# Module_BaseBoard.net
KiCad netlist of a schematic drawn in EAGLE
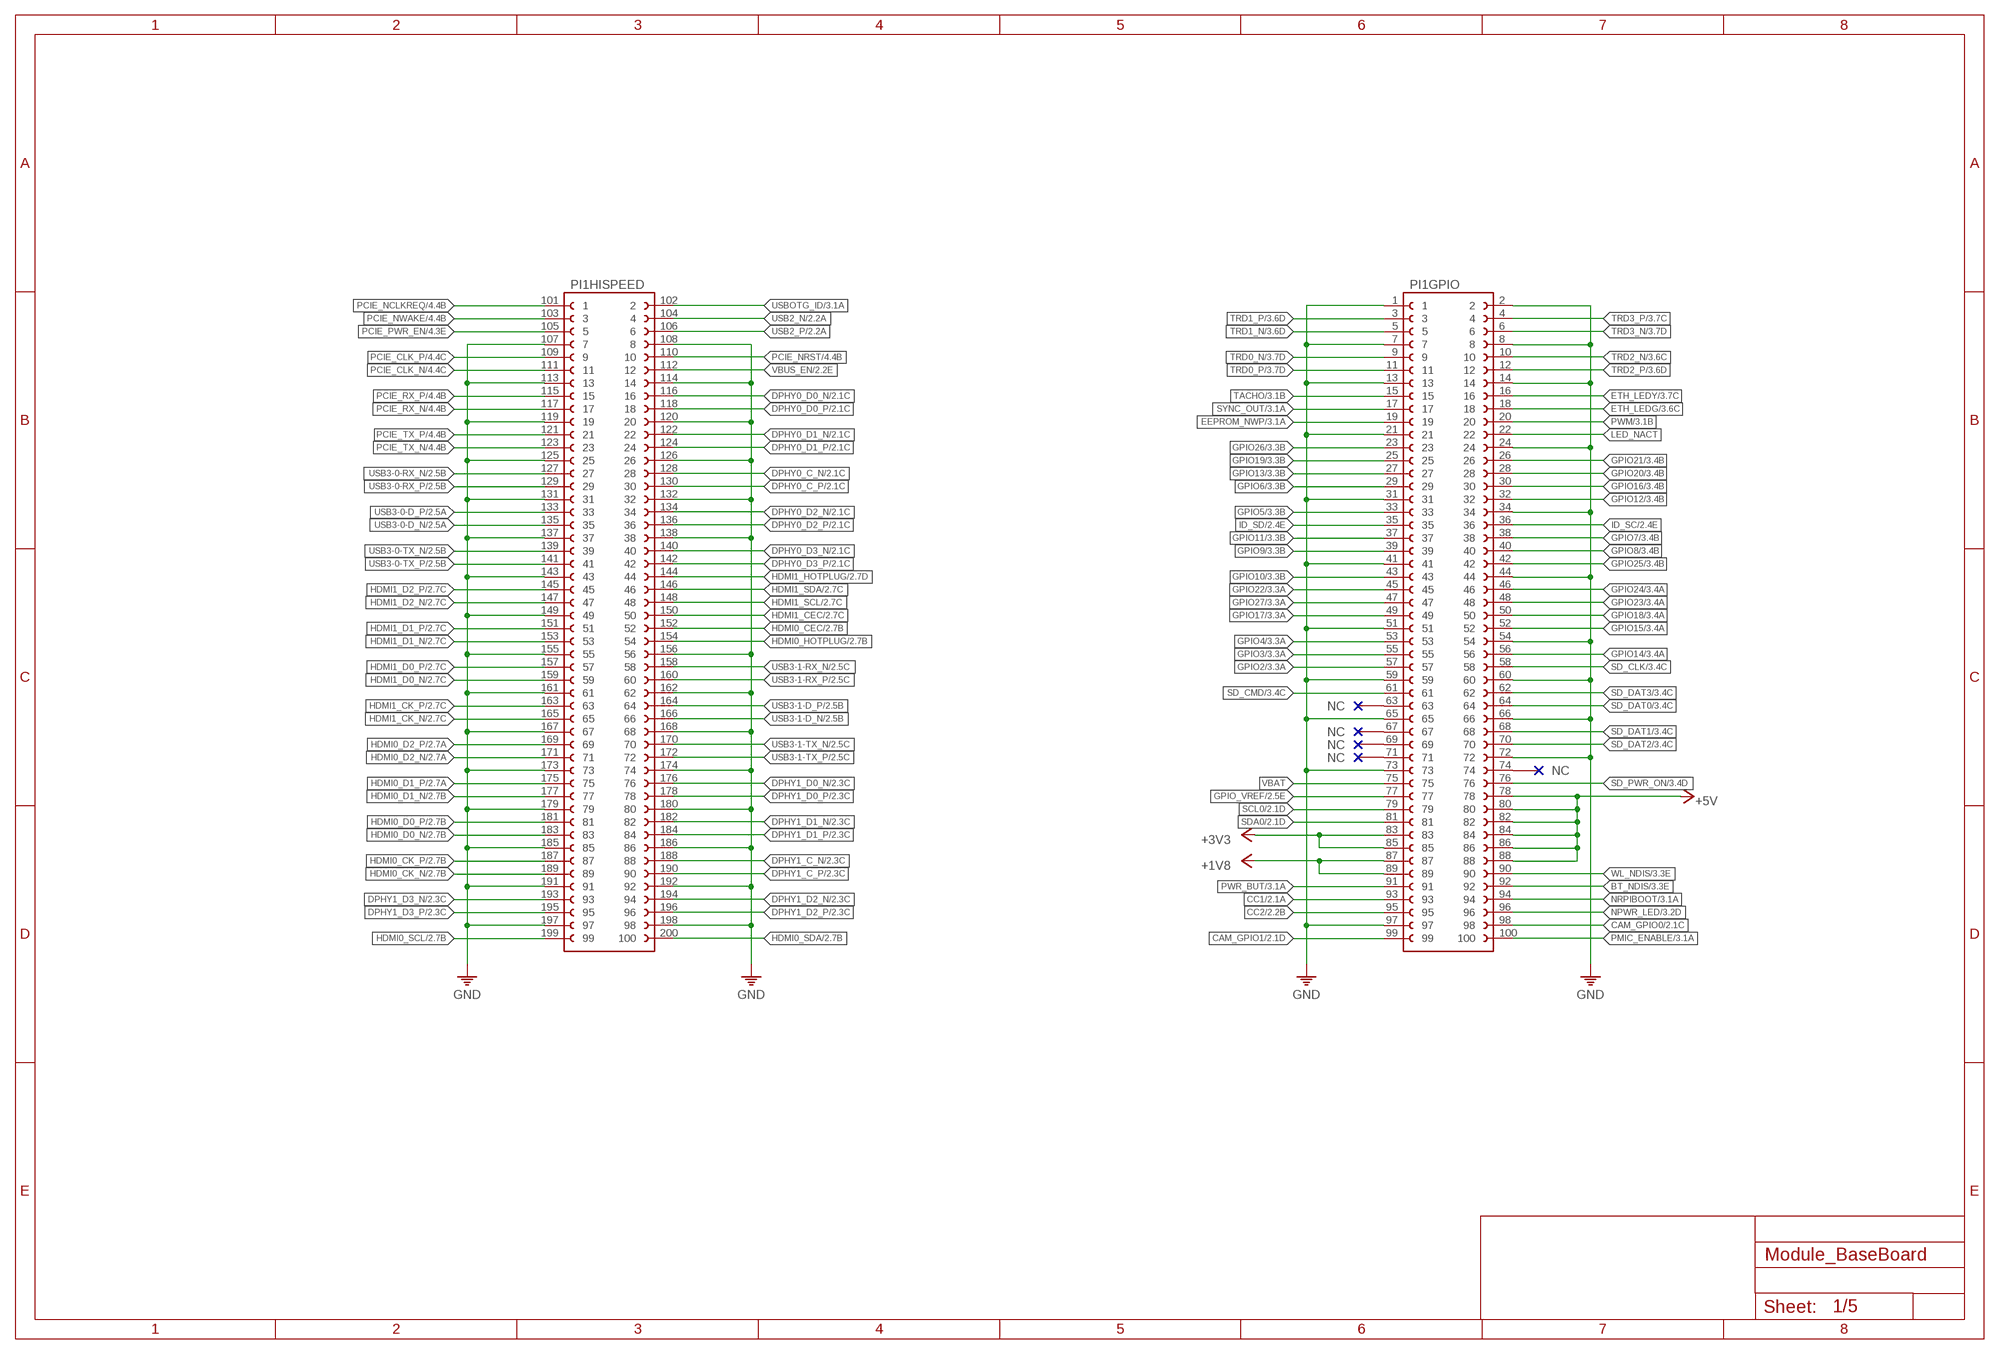
[diagram p0: schematic, sheet 1]
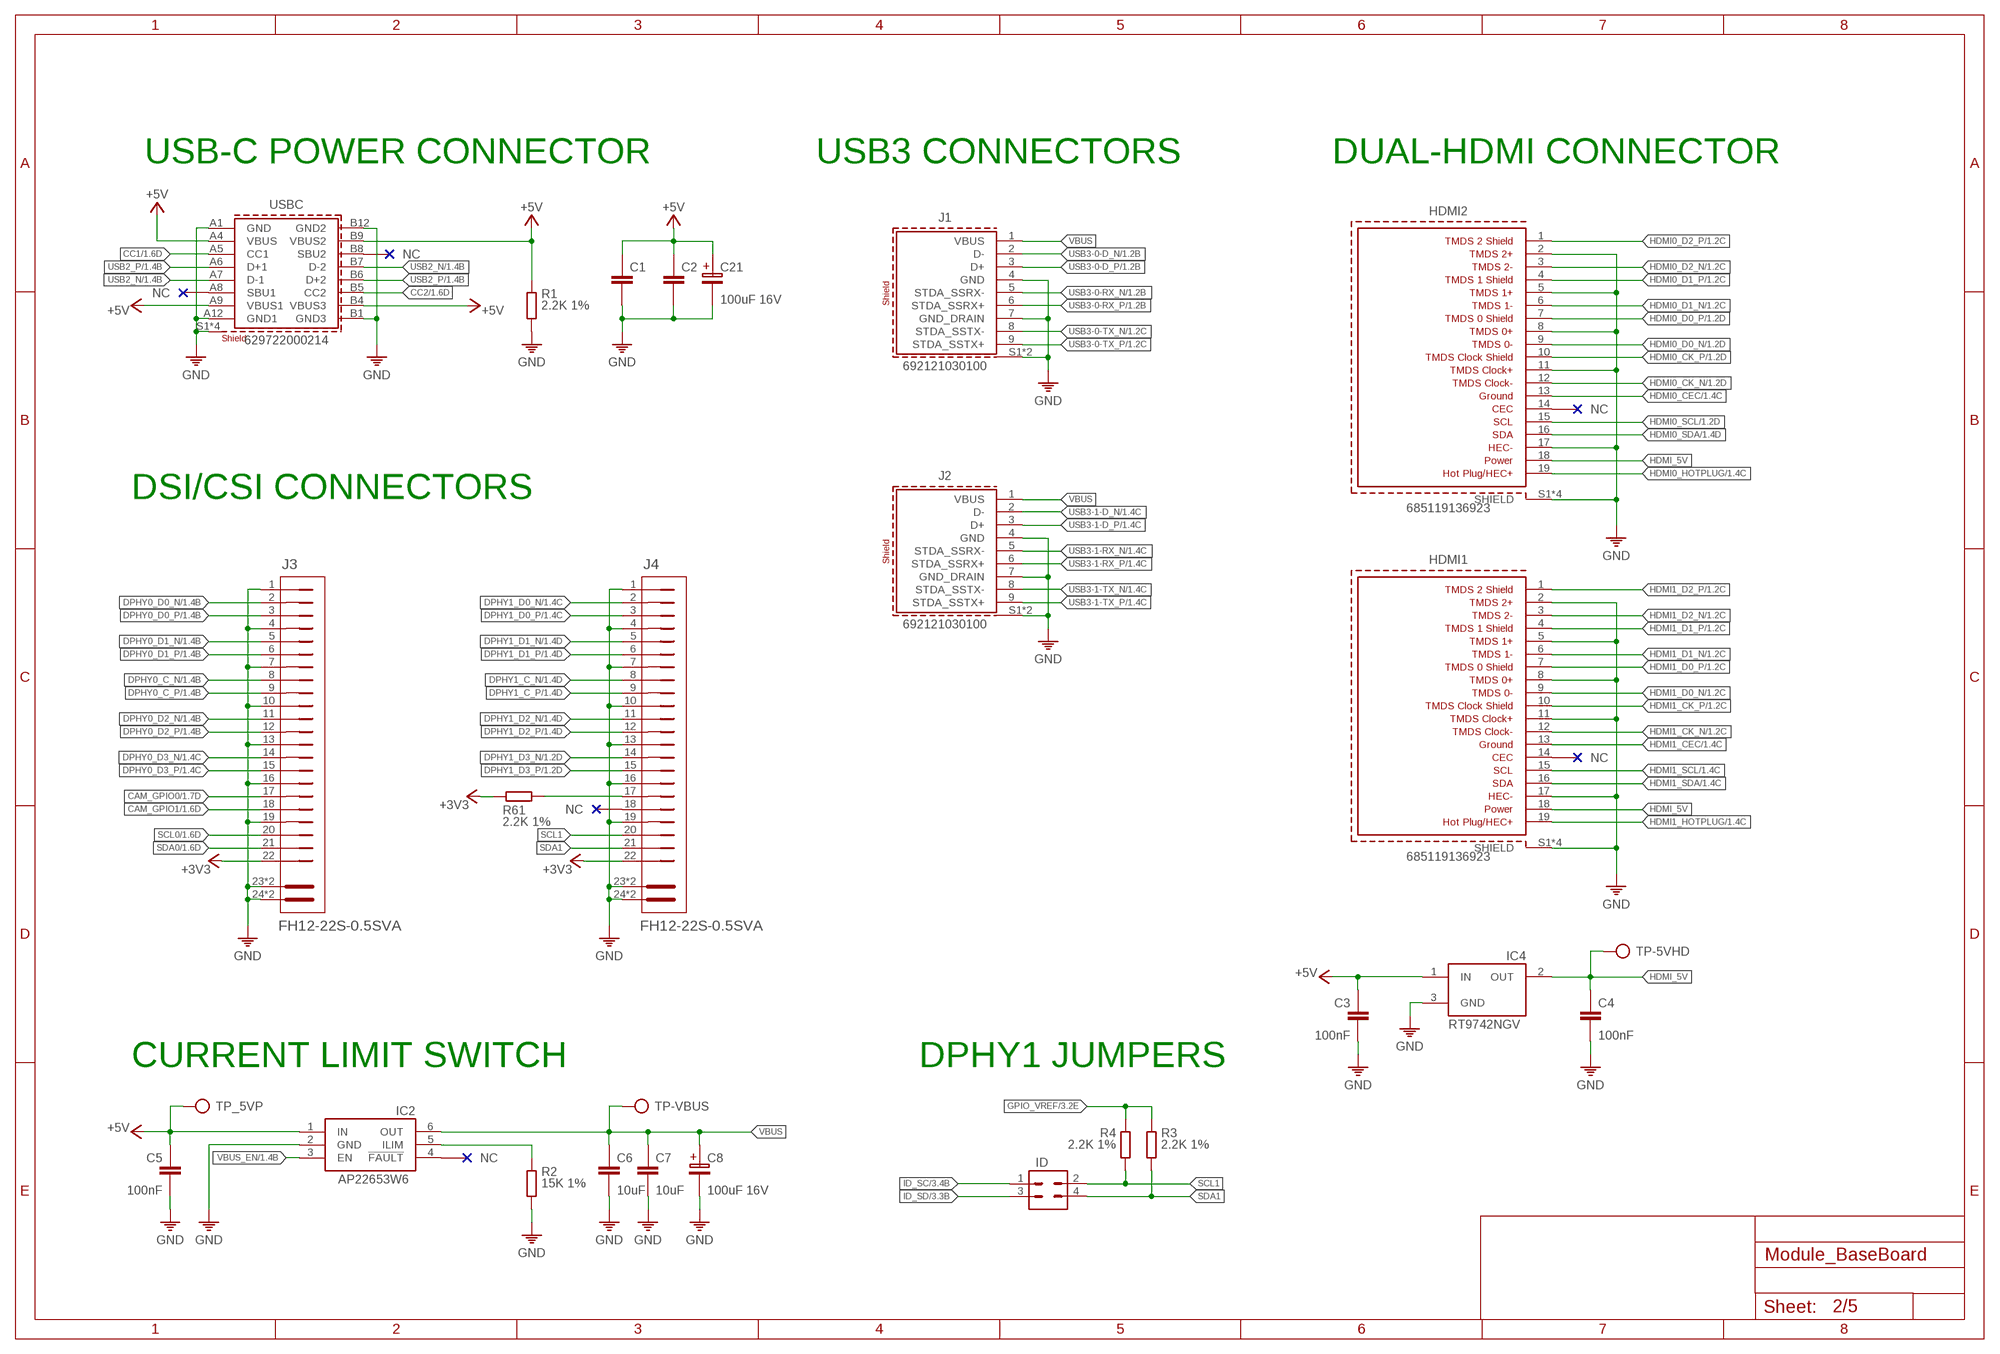
[diagram p1: schematic, sheet 2]
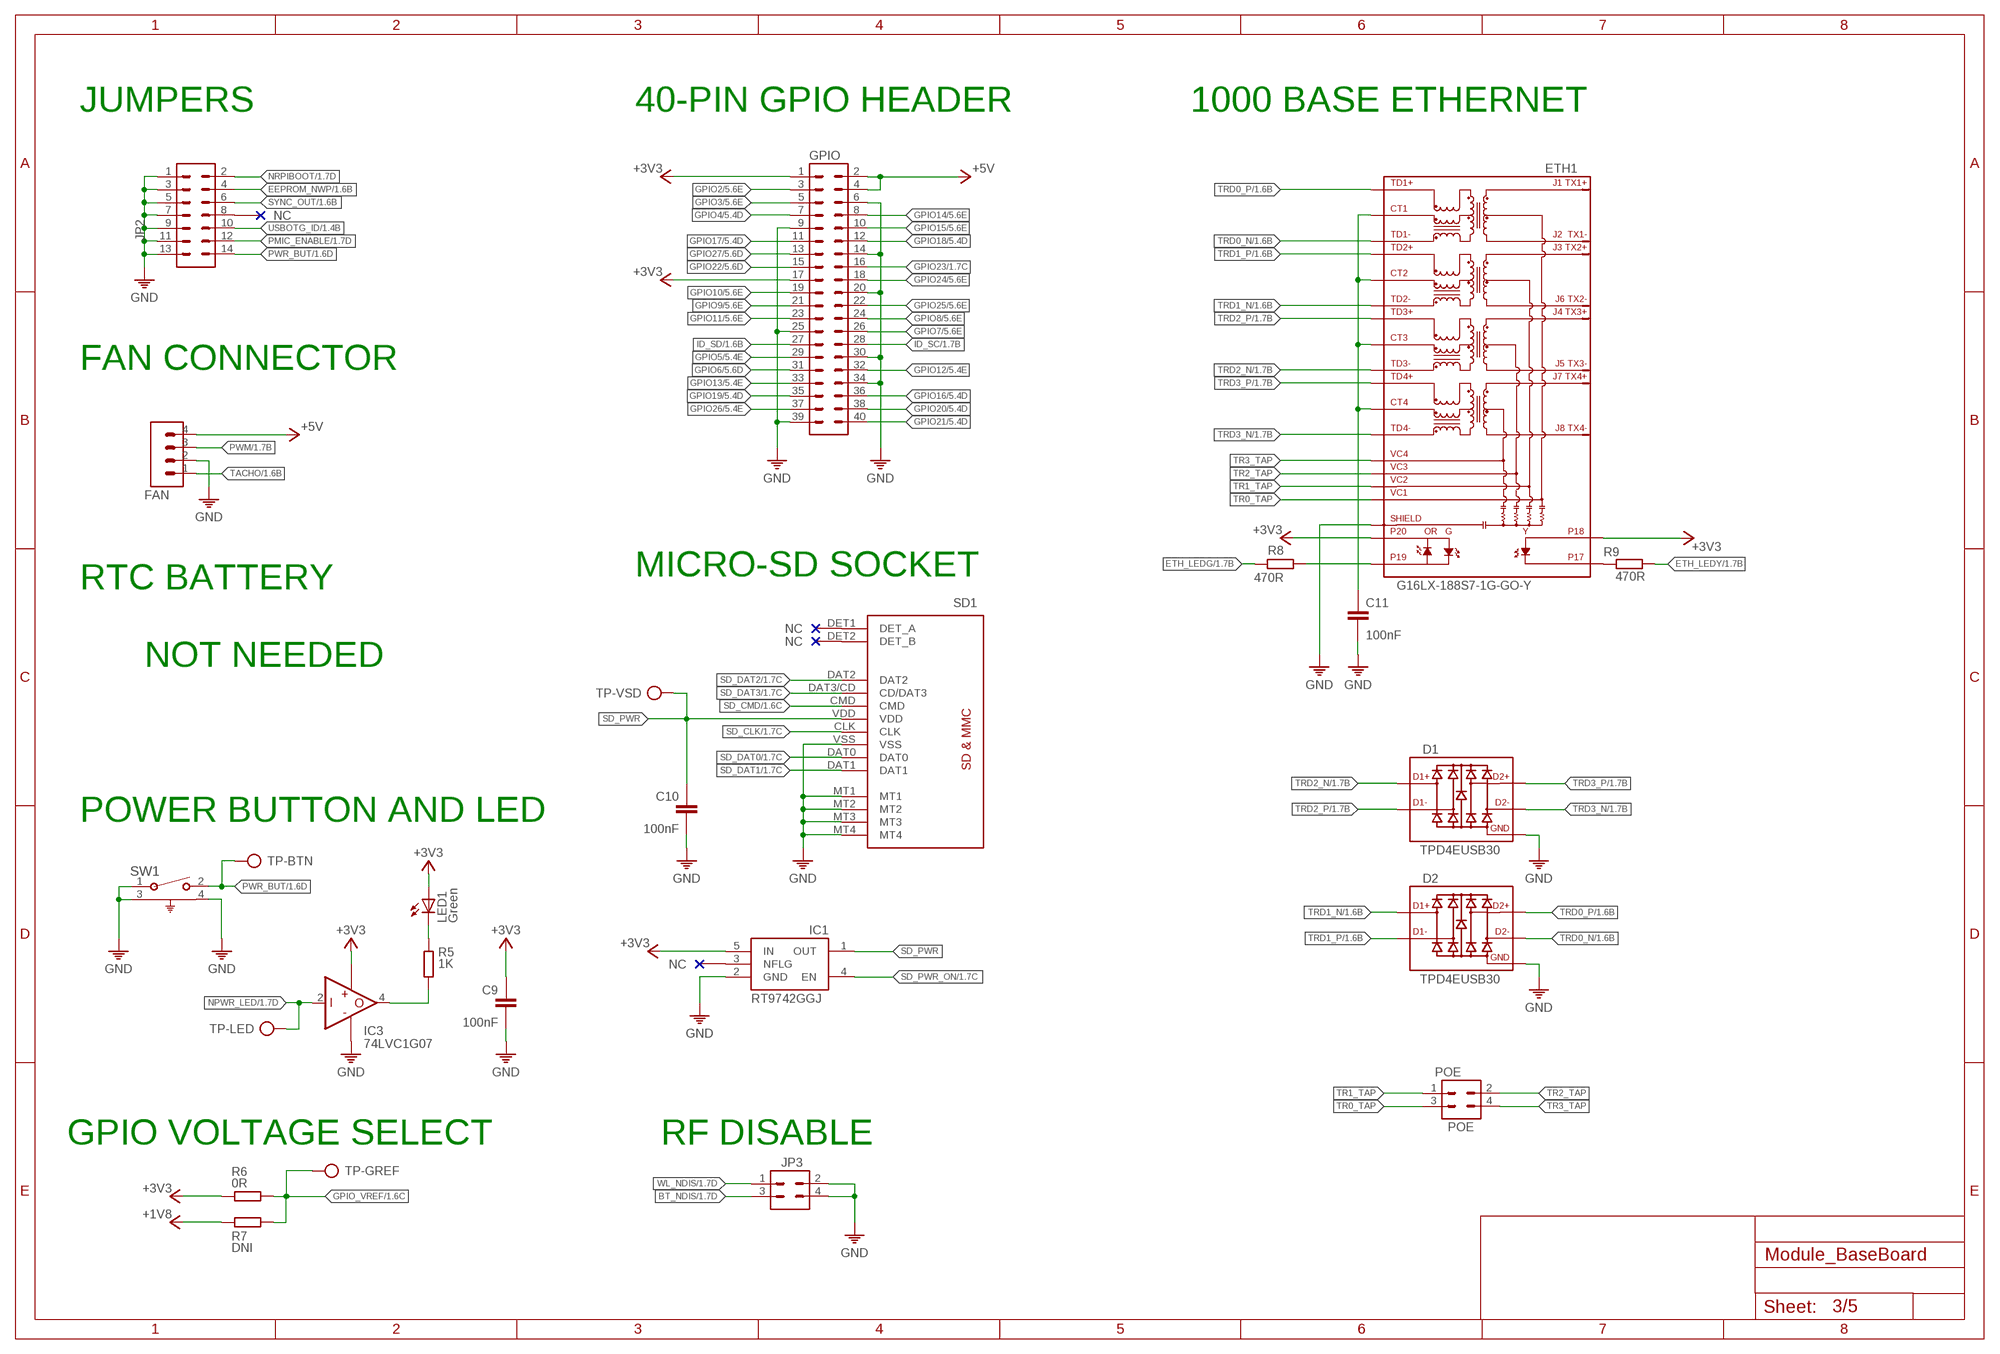
[diagram p2: schematic, sheet 3]
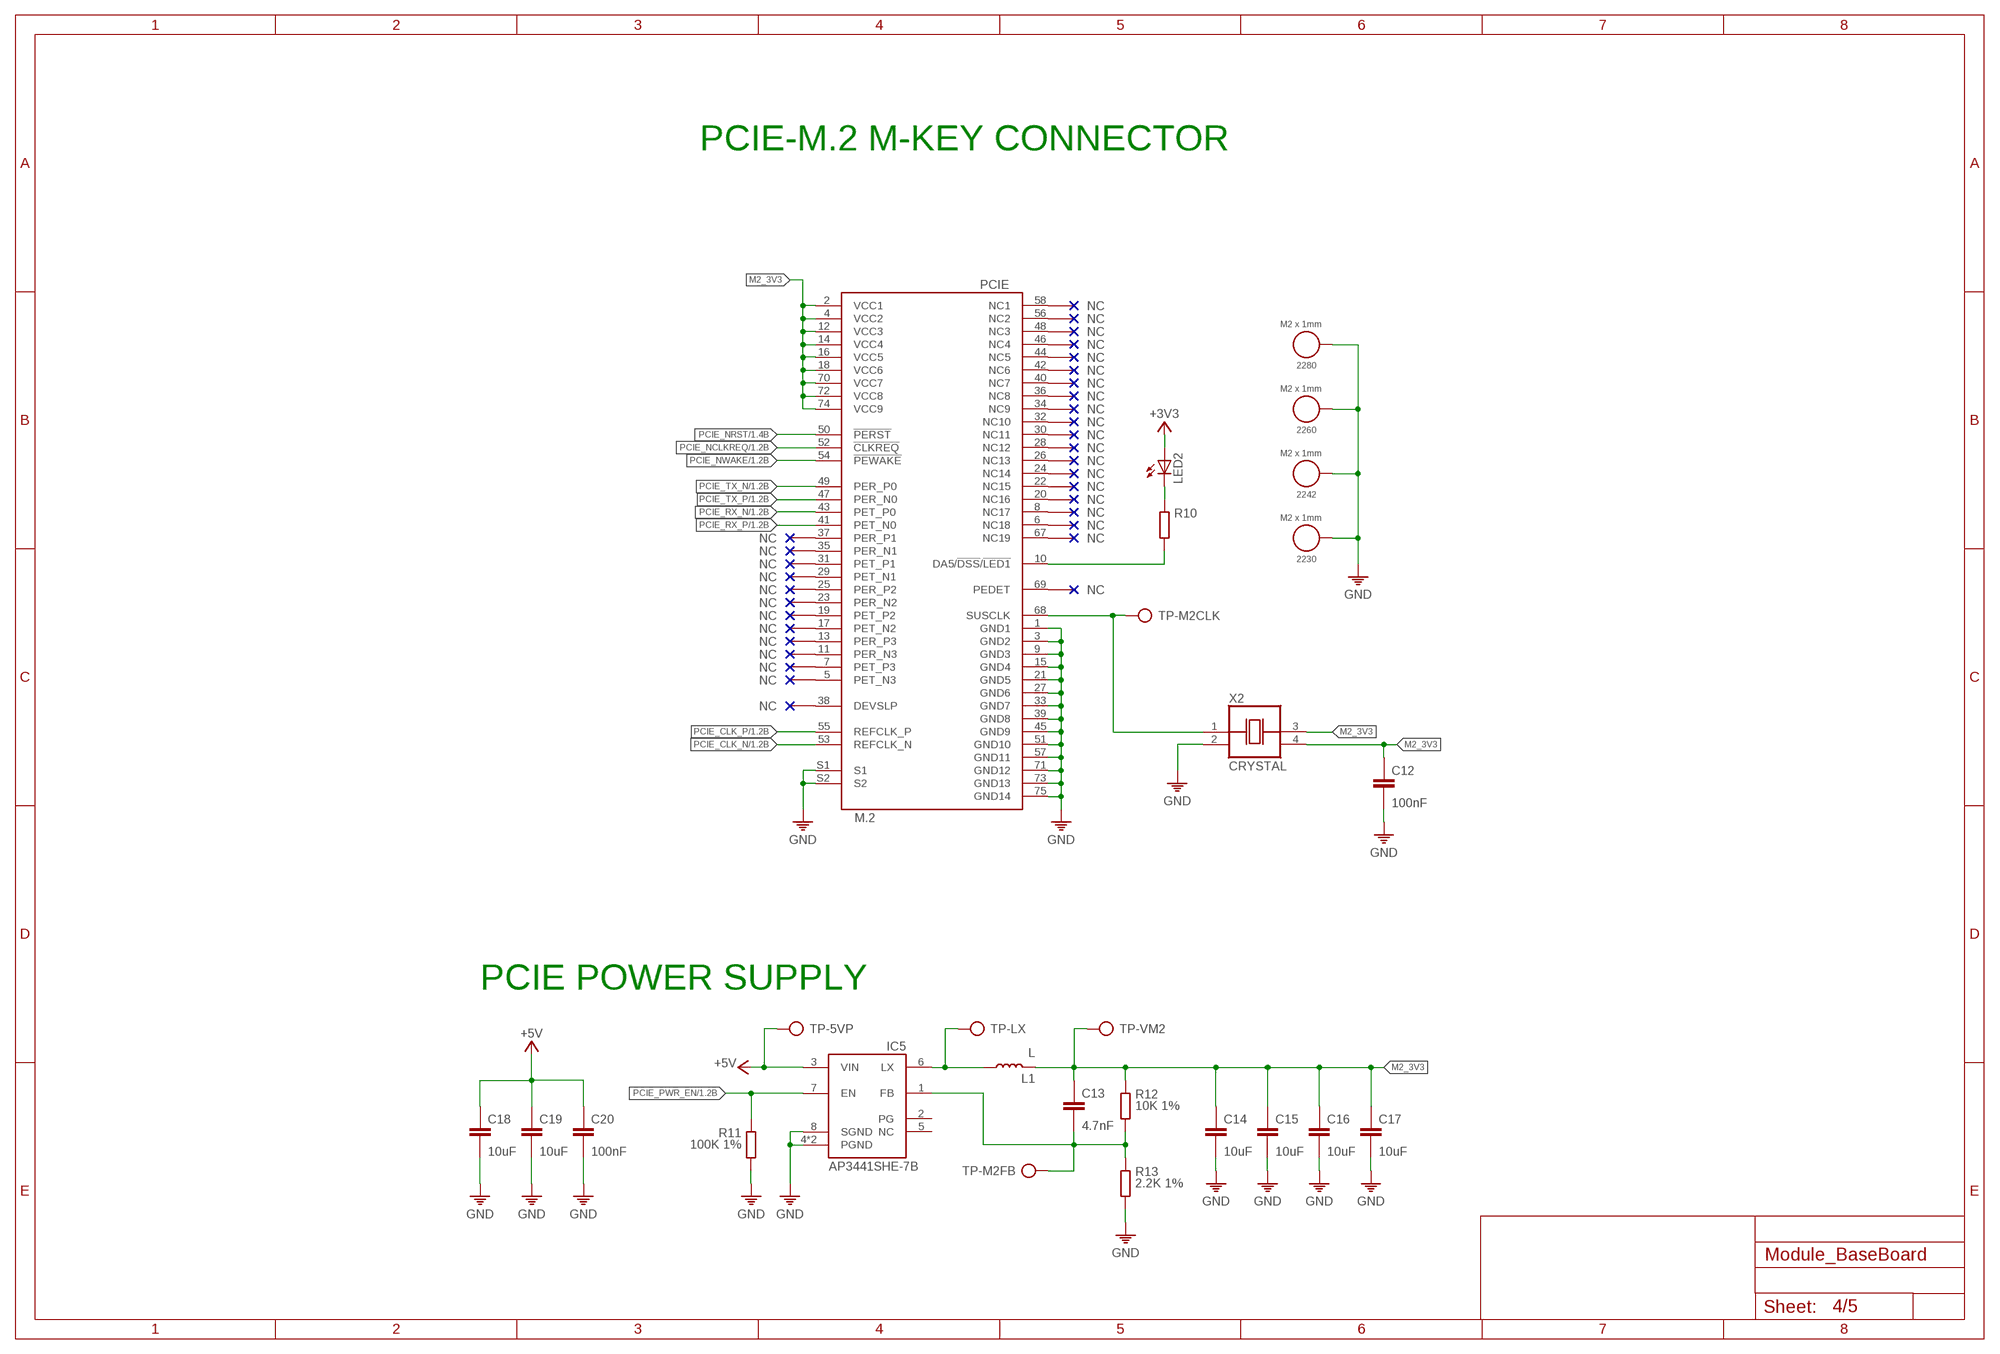
[diagram p3: schematic, sheet 4]
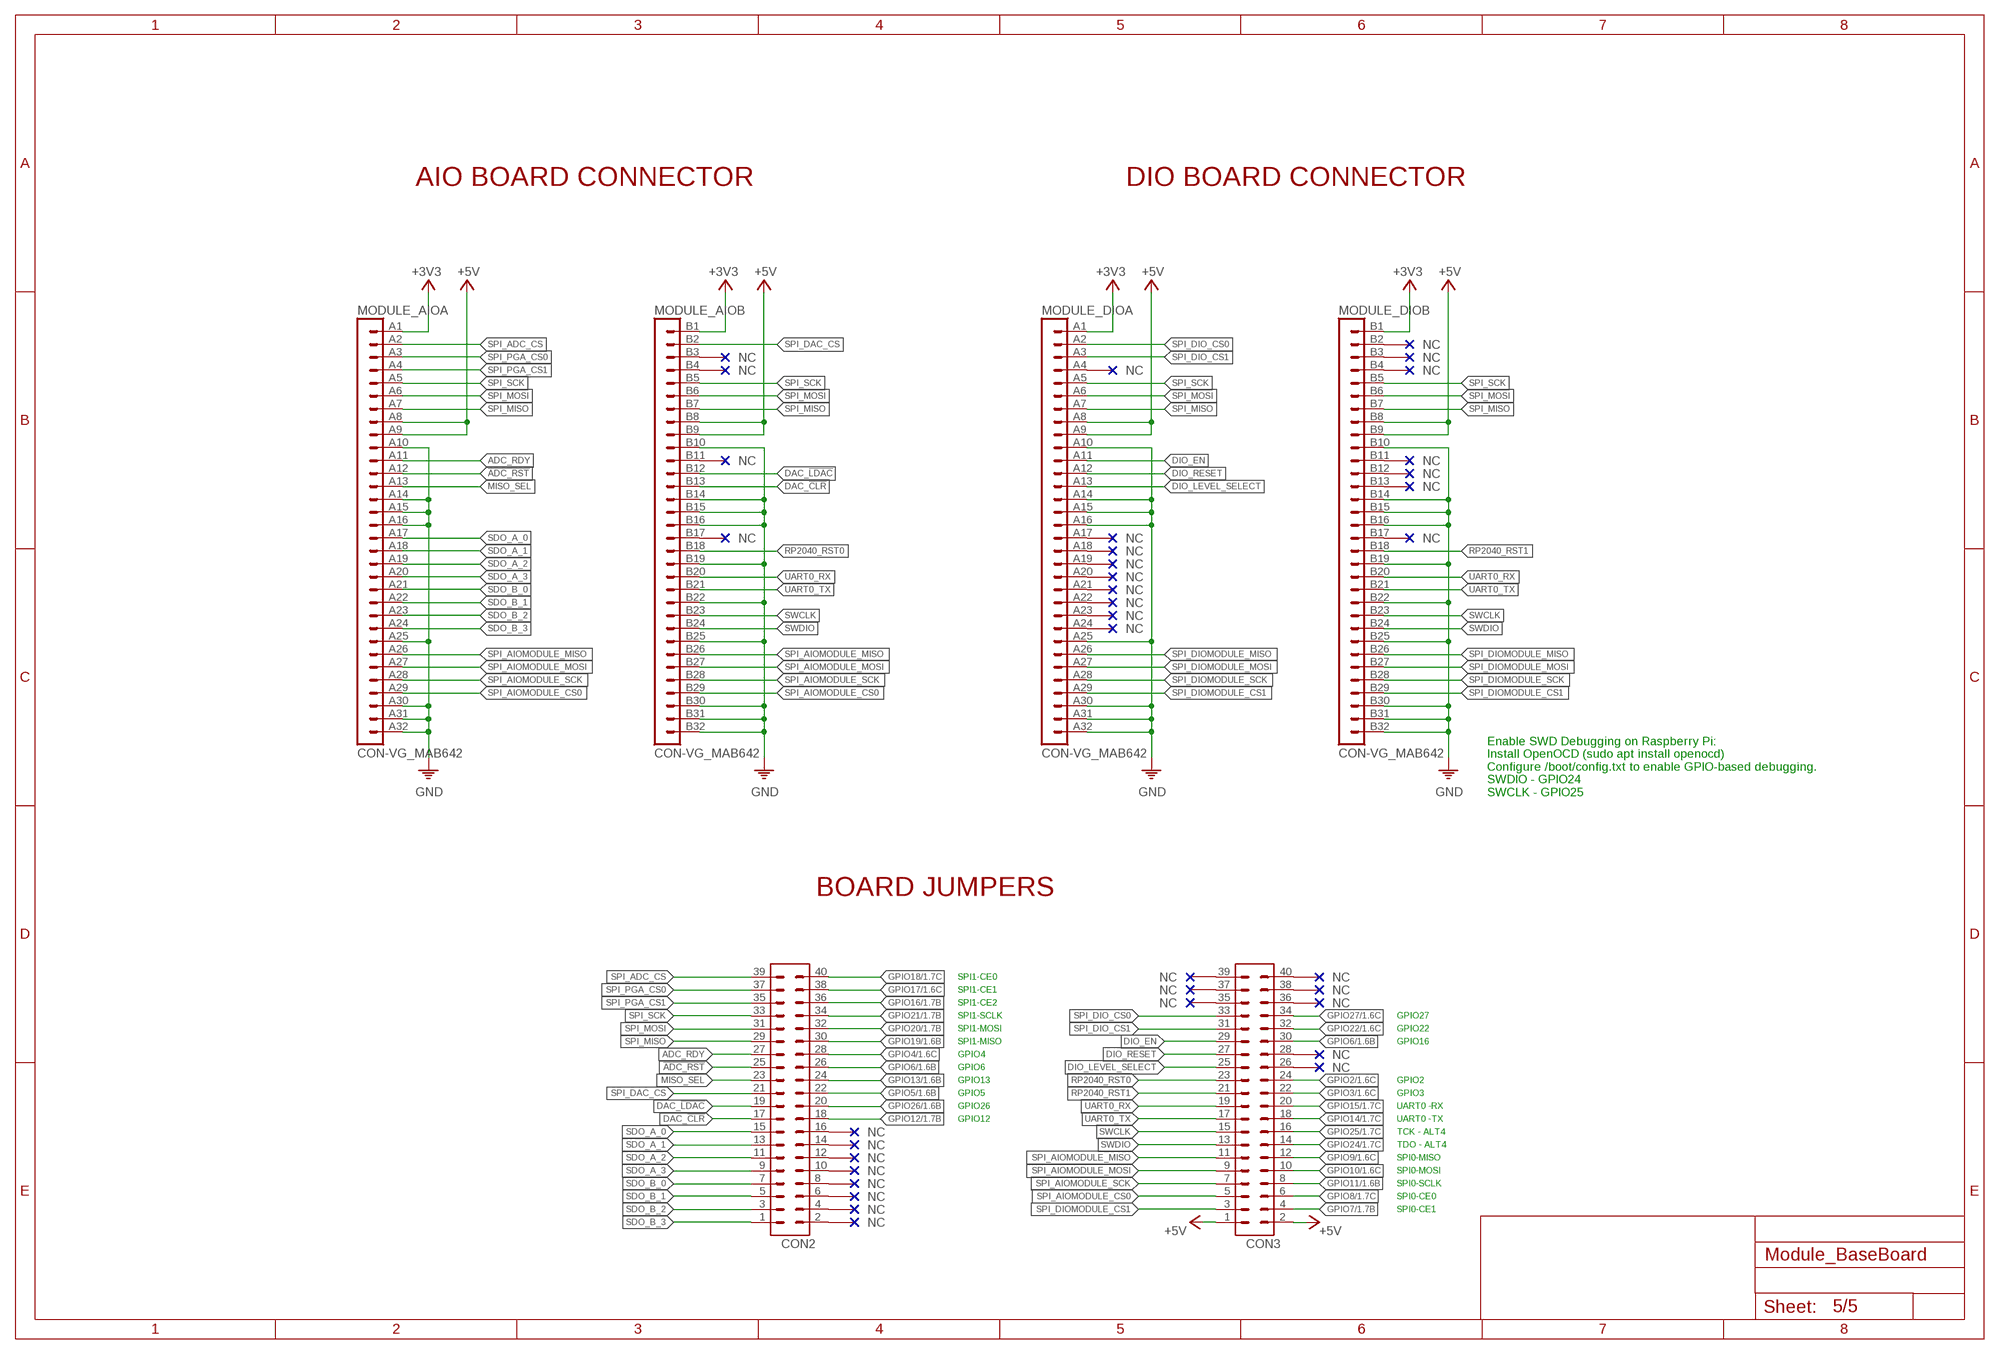
[diagram p4: schematic, sheet 5]

(export (version "E")
  (design (tool "Eeschema 10.0.6"))
  (components
    (comp (ref "PI1")
      (value "RASPBERRY_CM5")
      (footprint "eagle-import:CM5")
      (libsource (lib "eagle-import") (part "RASPBERRY_CM5"))
    )
    (comp (ref "2230")
      (value "M2 x 1mm")
      (footprint "eagle-import:WA-SMSI_9774010243")
      (libsource (lib "eagle-import") (part "WA-SMSI_9774XXX243_9774010243"))
    )
    (comp (ref "2242")
      (value "M2 x 1mm")
      (footprint "eagle-import:WA-SMSI_9774010243")
      (libsource (lib "eagle-import") (part "WA-SMSI_9774XXX243_9774010243"))
    )
    (comp (ref "2260")
      (value "M2 x 1mm")
      (footprint "eagle-import:WA-SMSI_9774010243")
      (libsource (lib "eagle-import") (part "WA-SMSI_9774XXX243_9774010243"))
    )
    (comp (ref "2280")
      (value "M2 x 1mm")
      (footprint "eagle-import:WA-SMSI_9774010243")
      (libsource (lib "eagle-import") (part "WA-SMSI_9774XXX243_9774010243"))
    )
    (comp (ref "C12")
      (value "100nF")
      (footprint "eagle-import:C0402")
      (libsource (lib "eagle-import") (part "C-0402"))
    )
    (comp (ref "C13")
      (value "4.7nF")
      (footprint "eagle-import:C0402")
      (libsource (lib "eagle-import") (part "C-0402"))
    )
    (comp (ref "C14")
      (value "10uF")
      (footprint "eagle-import:C0805")
      (libsource (lib "eagle-import") (part "C-0805"))
    )
    (comp (ref "C15")
      (value "10uF")
      (footprint "eagle-import:C0805")
      (libsource (lib "eagle-import") (part "C-0805"))
    )
    (comp (ref "C16")
      (value "10uF")
      (footprint "eagle-import:C0805")
      (libsource (lib "eagle-import") (part "C-0805"))
    )
    (comp (ref "C17")
      (value "10uF")
      (footprint "eagle-import:C0805")
      (libsource (lib "eagle-import") (part "C-0805"))
    )
    (comp (ref "C18")
      (value "10uF")
      (footprint "eagle-import:C0805")
      (libsource (lib "eagle-import") (part "C-0805"))
    )
    (comp (ref "C19")
      (value "10uF")
      (footprint "eagle-import:C0805")
      (libsource (lib "eagle-import") (part "C-0805"))
    )
    (comp (ref "C20")
      (value "100nF")
      (footprint "eagle-import:C0402")
      (libsource (lib "eagle-import") (part "C-0402"))
    )
    (comp (ref "IC5")
      (value "AP3441SHE-7B")
      (footprint "eagle-import:SON50P201X201X56-9T90X170N")
      (libsource (lib "eagle-import") (part "AP3441SHE-7B"))
    )
    (comp (ref "L1")
      (value "L")
      (footprint "eagle-import:SRR5228A")
      (libsource (lib "eagle-import") (part "L"))
    )
    (comp (ref "LED2")
      (value "LEDCHIPLED_0805")
      (footprint "eagle-import:CHIPLED_0805")
      (libsource (lib "eagle-import") (part "LEDCHIPLED_0805"))
    )
    (comp (ref "PCIE")
      (value "M.2")
      (footprint "eagle-import:M.2")
      (libsource (lib "eagle-import") (part "M.2"))
    )
    (comp (ref "R10")
      (value "R0402")
      (footprint "eagle-import:0402")
      (libsource (lib "eagle-import") (part "R0402"))
    )
    (comp (ref "R11")
      (value "100K 1%")
      (footprint "eagle-import:0402")
      (libsource (lib "eagle-import") (part "R0402"))
    )
    (comp (ref "R12")
      (value "10K 1%")
      (footprint "eagle-import:0402")
      (libsource (lib "eagle-import") (part "R0402"))
    )
    (comp (ref "R13")
      (value "2.2K 1%")
      (footprint "eagle-import:0402")
      (libsource (lib "eagle-import") (part "R0402"))
    )
    (comp (ref "TP-5VP")
      (value "TP")
      (footprint "eagle-import:TP")
      (libsource (lib "eagle-import") (part "TP"))
    )
    (comp (ref "TP-LX")
      (value "TP")
      (footprint "eagle-import:TP")
      (libsource (lib "eagle-import") (part "TP"))
    )
    (comp (ref "TP-M2CLK")
      (value "TP")
      (footprint "eagle-import:TP")
      (libsource (lib "eagle-import") (part "TP"))
    )
    (comp (ref "TP-M2FB")
      (value "TP")
      (footprint "eagle-import:TP")
      (libsource (lib "eagle-import") (part "TP"))
    )
    (comp (ref "TP-VM2")
      (value "TP")
      (footprint "eagle-import:TP")
      (libsource (lib "eagle-import") (part "TP"))
    )
    (comp (ref "X2")
      (value "CRYSTAL")
      (footprint "eagle-import:OSCCC500X320X130")
      (libsource (lib "eagle-import") (part "CRYSTAL"))
    )
    (comp (ref "CON2")
      (value "CON-2X20")
      (footprint "eagle-import:2X20")
      (libsource (lib "eagle-import") (part "CON-2X20"))
    )
    (comp (ref "CON3")
      (value "CON-2X20")
      (footprint "eagle-import:2X20")
      (libsource (lib "eagle-import") (part "CON-2X20"))
    )
    (comp (ref "MODULE_AIO")
      (value "CON-VG_MAB642")
      (footprint "eagle-import:CON-VG-MAB64-RECEPTACLE")
      (libsource (lib "eagle-import") (part "CON-VG_MAB642"))
    )
    (comp (ref "MODULE_DIO")
      (value "CON-VG_MAB642")
      (footprint "eagle-import:CON-VG-MAB64-RECEPTACLE")
      (libsource (lib "eagle-import") (part "CON-VG_MAB642"))
    )
    (comp (ref "C1")
      (value "C-0402")
      (footprint "eagle-import:C0402")
      (libsource (lib "eagle-import") (part "C-0402"))
    )
    (comp (ref "C2")
      (value "C-0402")
      (footprint "eagle-import:C0402")
      (libsource (lib "eagle-import") (part "C-0402"))
    )
    (comp (ref "C3")
      (value "100nF")
      (footprint "eagle-import:C0402")
      (libsource (lib "eagle-import") (part "C-0402"))
    )
    (comp (ref "C4")
      (value "100nF")
      (footprint "eagle-import:C0402")
      (libsource (lib "eagle-import") (part "C-0402"))
    )
    (comp (ref "C5")
      (value "100nF")
      (footprint "eagle-import:C0402")
      (libsource (lib "eagle-import") (part "C-0402"))
    )
    (comp (ref "C6")
      (value "10uF")
      (footprint "eagle-import:C0805")
      (libsource (lib "eagle-import") (part "C-0805"))
    )
    (comp (ref "C7")
      (value "10uF")
      (footprint "eagle-import:C0805")
      (libsource (lib "eagle-import") (part "C-0805"))
    )
    (comp (ref "C8")
      (value "100uF 16V")
      (footprint "eagle-import:100UF-16V")
      (libsource (lib "eagle-import") (part "CPOL"))
    )
    (comp (ref "C21")
      (value "100uF 16V")
      (footprint "eagle-import:100UF-16V")
      (libsource (lib "eagle-import") (part "CPOL"))
    )
    (comp (ref "HDMI1")
      (value "685119136923")
      (footprint "eagle-import:685119136923")
      (libsource (lib "eagle-import") (part "685119136923"))
    )
    (comp (ref "HDMI2")
      (value "685119136923")
      (footprint "eagle-import:685119136923")
      (libsource (lib "eagle-import") (part "685119136923"))
    )
    (comp (ref "IC2")
      (value "AP22653W6")
      (footprint "eagle-import:SOT23-6")
      (libsource (lib "eagle-import") (part "AP22653W6"))
    )
    (comp (ref "IC4")
      (value "RT9742NGV")
      (footprint "eagle-import:SOT23")
      (libsource (lib "eagle-import") (part "RT9742NGV"))
    )
    (comp (ref "ID")
      (value "CON-2X2")
      (footprint "eagle-import:2X2")
      (libsource (lib "eagle-import") (part "CON-2X2"))
    )
    (comp (ref "J1")
      (value "692121030100")
      (footprint "eagle-import:692121030100")
      (libsource (lib "eagle-import") (part "692121030100"))
    )
    (comp (ref "J2")
      (value "692121030100")
      (footprint "eagle-import:692121030100")
      (libsource (lib "eagle-import") (part "692121030100"))
    )
    (comp (ref "J3")
      (value "FH12-22S-0.5SVA")
      (footprint "eagle-import:FH12-22S-0.5SH")
      (libsource (lib "eagle-import") (part "FH12-22S-0.5SVA"))
    )
    (comp (ref "J4")
      (value "FH12-22S-0.5SVA")
      (footprint "eagle-import:FH12-22S-0.5SH")
      (libsource (lib "eagle-import") (part "FH12-22S-0.5SVA"))
    )
    (comp (ref "R1")
      (value "2.2K 1%")
      (footprint "eagle-import:0402")
      (libsource (lib "eagle-import") (part "R0402"))
    )
    (comp (ref "R2")
      (value "15K 1%")
      (footprint "eagle-import:0402")
      (libsource (lib "eagle-import") (part "R0402"))
    )
    (comp (ref "R3")
      (value "2.2K 1%")
      (footprint "eagle-import:0402")
      (libsource (lib "eagle-import") (part "R0402"))
    )
    (comp (ref "R4")
      (value "2.2K 1%")
      (footprint "eagle-import:0402")
      (libsource (lib "eagle-import") (part "R0402"))
    )
    (comp (ref "R61")
      (value "2.2K 1%")
      (footprint "eagle-import:0402")
      (libsource (lib "eagle-import") (part "ds_passive_46685041_R0402"))
    )
    (comp (ref "TP-5VHD")
      (value "TP")
      (footprint "eagle-import:TP")
      (libsource (lib "eagle-import") (part "TP"))
    )
    (comp (ref "TP-VBUS")
      (value "TP")
      (footprint "eagle-import:TP")
      (libsource (lib "eagle-import") (part "TP"))
    )
    (comp (ref "TP_5VP")
      (value "TP")
      (footprint "eagle-import:TP")
      (libsource (lib "eagle-import") (part "TP"))
    )
    (comp (ref "USBC")
      (value "629722000214")
      (footprint "eagle-import:629722000214")
      (libsource (lib "eagle-import") (part "629722000214"))
    )
    (comp (ref "C9")
      (value "100nF")
      (footprint "eagle-import:C0402")
      (libsource (lib "eagle-import") (part "C-0402"))
    )
    (comp (ref "C10")
      (value "100nF")
      (footprint "eagle-import:C0402")
      (libsource (lib "eagle-import") (part "C-0402"))
    )
    (comp (ref "C11")
      (value "100nF")
      (footprint "eagle-import:C0402")
      (libsource (lib "eagle-import") (part "C-0402"))
    )
    (comp (ref "D1")
      (value "TPD4EUSB30")
      (footprint "eagle-import:USON")
      (libsource (lib "eagle-import") (part "TPD4EUSB30"))
    )
    (comp (ref "D2")
      (value "TPD4EUSB30")
      (footprint "eagle-import:USON")
      (libsource (lib "eagle-import") (part "TPD4EUSB30"))
    )
    (comp (ref "ETH1")
      (value "G16LX-188S7-1G-GO-Y")
      (footprint "eagle-import:MAGJACK_POE")
      (libsource (lib "eagle-import") (part "MAGJACK-POE"))
    )
    (comp (ref "FAN")
      (value "CON-1X4")
      (footprint "eagle-import:1X4")
      (libsource (lib "eagle-import") (part "CON-1X4"))
    )
    (comp (ref "GPIO")
      (value "CON-2X20")
      (footprint "eagle-import:2X20")
      (libsource (lib "eagle-import") (part "CON-2X20"))
    )
    (comp (ref "IC1")
      (value "RT9742GGJ")
      (footprint "eagle-import:SOT23-5")
      (libsource (lib "eagle-import") (part "RT9742GGJ5"))
    )
    (comp (ref "IC3")
      (value "74LVC1G07")
      (footprint "eagle-import:SOT23-5")
      (libsource (lib "eagle-import") (part "74LVC1G07"))
    )
    (comp (ref "JP2")
      (value "CON-2X7")
      (footprint "eagle-import:2X7")
      (libsource (lib "eagle-import") (part "CON-2X7"))
    )
    (comp (ref "JP3")
      (value "CON-2X2")
      (footprint "eagle-import:2X2")
      (libsource (lib "eagle-import") (part "CON-2X2"))
    )
    (comp (ref "LED1")
      (value "Green")
      (footprint "eagle-import:CHIPLED_0805")
      (libsource (lib "eagle-import") (part "LEDCHIPLED_0805"))
    )
    (comp (ref "POE")
      (value "POE")
      (footprint "eagle-import:2X2")
      (libsource (lib "eagle-import") (part "CON-2X2"))
    )
    (comp (ref "R5")
      (value "1K")
      (footprint "eagle-import:0402")
      (libsource (lib "eagle-import") (part "R0402"))
    )
    (comp (ref "R6")
      (value "0R")
      (footprint "eagle-import:0402")
      (libsource (lib "eagle-import") (part "R0402"))
    )
    (comp (ref "R7")
      (value "DNI")
      (footprint "eagle-import:0402")
      (libsource (lib "eagle-import") (part "R0402"))
    )
    (comp (ref "R8")
      (value "470R")
      (footprint "eagle-import:0402")
      (libsource (lib "eagle-import") (part "R0402"))
    )
    (comp (ref "R9")
      (value "470R")
      (footprint "eagle-import:0402")
      (libsource (lib "eagle-import") (part "R0402"))
    )
    (comp (ref "SD1")
      (value "MICRO-SD")
      (footprint "eagle-import:MICROSD")
      (libsource (lib "eagle-import") (part "MICRO-SD"))
    )
    (comp (ref "SW1")
      (value "1825027-8")
      (footprint "eagle-import:SW2_1825027-C_TEC")
      (fields (field (name "COPYRIGHT") "Copyright (C) 2025 Ultra Librarian. All rights reserved."))
      (libsource (lib "eagle-import") (part "1825027-8"))
    )
    (comp (ref "TP-BTN")
      (value "TP")
      (footprint "eagle-import:TP")
      (libsource (lib "eagle-import") (part "TP"))
    )
    (comp (ref "TP-GREF")
      (value "TP")
      (footprint "eagle-import:TP")
      (libsource (lib "eagle-import") (part "TP"))
    )
    (comp (ref "TP-LED")
      (value "TP")
      (footprint "eagle-import:TP")
      (libsource (lib "eagle-import") (part "TP"))
    )
    (comp (ref "TP-VSD")
      (value "TP")
      (footprint "eagle-import:TP")
      (libsource (lib "eagle-import") (part "TP"))
    )
  )
  (nets
    (net (code "1") (name "+1V8") (class "Default")
      (node (ref "PI1") (pin "87") (pinfunction "87_87") (pintype "passive"))
      (node (ref "PI1") (pin "89") (pinfunction "89_89") (pintype "passive"))
      (node (ref "R7") (pin "1") (pinfunction "1_1") (pintype "passive"))
    )
    (net (code "2") (name "+3V3") (class "Default")
      (node (ref "C9") (pin "1") (pinfunction "1_1") (pintype "passive"))
      (node (ref "ETH1") (pin "18") (pinfunction "P18_18") (pintype "bidirectional"))
      (node (ref "ETH1") (pin "20") (pinfunction "P20_20") (pintype "bidirectional"))
      (node (ref "GPIO") (pin "1") (pinfunction "1_1") (pintype "bidirectional"))
      (node (ref "GPIO") (pin "17") (pinfunction "17_17") (pintype "bidirectional"))
      (node (ref "IC1") (pin "5") (pinfunction "IN_5") (pintype "power_in"))
      (node (ref "IC3") (pin "5") (pinfunction "VCC_5") (pintype "bidirectional"))
      (node (ref "J3") (pin "22") (pinfunction "22_22") (pintype "passive"))
      (node (ref "J4") (pin "22") (pinfunction "22_22") (pintype "passive"))
      (node (ref "LED1") (pin "A") (pinfunction "A_A") (pintype "passive"))
      (node (ref "LED2") (pin "A") (pinfunction "A_A") (pintype "passive"))
      (node (ref "MODULE_AIO") (pin "A1") (pinfunction "1_A1") (pintype "passive"))
      (node (ref "MODULE_AIO") (pin "B1") (pinfunction "1_B1") (pintype "passive"))
      (node (ref "MODULE_DIO") (pin "A1") (pinfunction "1_A1") (pintype "passive"))
      (node (ref "MODULE_DIO") (pin "B1") (pinfunction "1_B1") (pintype "passive"))
      (node (ref "PI1") (pin "83") (pinfunction "83_83") (pintype "passive"))
      (node (ref "PI1") (pin "85") (pinfunction "85_85") (pintype "passive"))
      (node (ref "R6") (pin "1") (pinfunction "1_1") (pintype "passive"))
      (node (ref "R61") (pin "2") (pinfunction "2_2") (pintype "passive"))
    )
    (net (code "3") (name "+5V") (class "Default")
      (node (ref "C1") (pin "1") (pinfunction "1_1") (pintype "passive"))
      (node (ref "C18") (pin "1") (pinfunction "1_1") (pintype "passive"))
      (node (ref "C19") (pin "1") (pinfunction "1_1") (pintype "passive"))
      (node (ref "C2") (pin "1") (pinfunction "1_1") (pintype "passive"))
      (node (ref "C20") (pin "1") (pinfunction "1_1") (pintype "passive"))
      (node (ref "C21") (pin "1") (pinfunction "1_1") (pintype "passive"))
      (node (ref "C3") (pin "1") (pinfunction "1_1") (pintype "passive"))
      (node (ref "C5") (pin "1") (pinfunction "1_1") (pintype "passive"))
      (node (ref "CON3") (pin "1") (pinfunction "1_1") (pintype "bidirectional"))
      (node (ref "CON3") (pin "2") (pinfunction "2_2") (pintype "bidirectional"))
      (node (ref "FAN") (pin "4") (pinfunction "P$4_4") (pintype "bidirectional"))
      (node (ref "GPIO") (pin "2") (pinfunction "2_2") (pintype "bidirectional"))
      (node (ref "GPIO") (pin "4") (pinfunction "4_4") (pintype "bidirectional"))
      (node (ref "IC2") (pin "1") (pinfunction "IN_1") (pintype "bidirectional"))
      (node (ref "IC4") (pin "1") (pinfunction "IN_1") (pintype "power_in"))
      (node (ref "IC5") (pin "3") (pinfunction "VIN_3") (pintype "power_in"))
      (node (ref "MODULE_AIO") (pin "A8") (pinfunction "8_A8") (pintype "passive"))
      (node (ref "MODULE_AIO") (pin "A9") (pinfunction "9_A9") (pintype "passive"))
      (node (ref "MODULE_AIO") (pin "B8") (pinfunction "8_B8") (pintype "passive"))
      (node (ref "MODULE_AIO") (pin "B9") (pinfunction "9_B9") (pintype "passive"))
      (node (ref "MODULE_DIO") (pin "A8") (pinfunction "8_A8") (pintype "passive"))
      (node (ref "MODULE_DIO") (pin "A9") (pinfunction "9_A9") (pintype "passive"))
      (node (ref "MODULE_DIO") (pin "B8") (pinfunction "8_B8") (pintype "passive"))
      (node (ref "MODULE_DIO") (pin "B9") (pinfunction "9_B9") (pintype "passive"))
      (node (ref "PI1") (pin "78") (pinfunction "78_78") (pintype "passive"))
      (node (ref "PI1") (pin "80") (pinfunction "80_80") (pintype "passive"))
      (node (ref "PI1") (pin "82") (pinfunction "82_82") (pintype "passive"))
      (node (ref "PI1") (pin "84") (pinfunction "84_84") (pintype "passive"))
      (node (ref "PI1") (pin "86") (pinfunction "86_86") (pintype "passive"))
      (node (ref "PI1") (pin "88") (pinfunction "88_88") (pintype "passive"))
      (node (ref "R1") (pin "1") (pinfunction "1_1") (pintype "passive"))
      (node (ref "TP-5VP") (pin "TP") (pinfunction "P$1_TP") (pintype "bidirectional"))
      (node (ref "TP_5VP") (pin "TP") (pinfunction "P$1_TP") (pintype "bidirectional"))
      (node (ref "USBC") (pin "A4") (pinfunction "VBUS_A4") (pintype "passive"))
      (node (ref "USBC") (pin "A9") (pinfunction "VBUS1_A9") (pintype "passive"))
      (node (ref "USBC") (pin "B4") (pinfunction "VBUS3_B4") (pintype "passive"))
      (node (ref "USBC") (pin "B9") (pinfunction "VBUS2_B9") (pintype "passive"))
    )
    (net (code "4") (name "ADC_RDY") (class "Default")
      (node (ref "CON2") (pin "27") (pinfunction "27_27") (pintype "bidirectional"))
      (node (ref "MODULE_AIO") (pin "A11") (pinfunction "11_A11") (pintype "passive"))
    )
    (net (code "5") (name "BT_NDIS") (class "Default")
      (node (ref "JP3") (pin "3") (pinfunction "3_3") (pintype "bidirectional"))
      (node (ref "PI1") (pin "92") (pinfunction "92_92") (pintype "passive"))
    )
    (net (code "6") (name "CAM_GPIO0") (class "Default")
      (node (ref "J3") (pin "17") (pinfunction "17_17") (pintype "passive"))
      (node (ref "PI1") (pin "98") (pinfunction "98_98") (pintype "passive"))
    )
    (net (code "7") (name "CAM_GPIO1") (class "Default")
      (node (ref "J3") (pin "18") (pinfunction "18_18") (pintype "passive"))
      (node (ref "PI1") (pin "99") (pinfunction "99_99") (pintype "passive"))
    )
    (net (code "8") (name "CC1") (class "Default")
      (node (ref "PI1") (pin "93") (pinfunction "93_93") (pintype "passive"))
      (node (ref "USBC") (pin "A5") (pinfunction "CC1_A5") (pintype "passive"))
    )
    (net (code "9") (name "CC2") (class "Default")
      (node (ref "PI1") (pin "95") (pinfunction "95_95") (pintype "passive"))
      (node (ref "USBC") (pin "B5") (pinfunction "CC2_B5") (pintype "passive"))
    )
    (net (code "10") (name "DAC_~{CLR}") (class "Default")
      (node (ref "CON2") (pin "17") (pinfunction "17_17") (pintype "bidirectional"))
      (node (ref "MODULE_AIO") (pin "B13") (pinfunction "13_B13") (pintype "passive"))
    )
    (net (code "11") (name "DAC_~{LDAC}") (class "Default")
      (node (ref "CON2") (pin "19") (pinfunction "19_19") (pintype "bidirectional"))
      (node (ref "MODULE_AIO") (pin "B12") (pinfunction "12_B12") (pintype "passive"))
    )
    (net (code "12") (name "DIO_EN") (class "Default")
      (node (ref "CON3") (pin "29") (pinfunction "29_29") (pintype "bidirectional"))
      (node (ref "MODULE_DIO") (pin "A11") (pinfunction "11_A11") (pintype "passive"))
    )
    (net (code "13") (name "DIO_LEVEL_SELECT") (class "Default")
      (node (ref "CON3") (pin "25") (pinfunction "25_25") (pintype "bidirectional"))
      (node (ref "MODULE_DIO") (pin "A13") (pinfunction "13_A13") (pintype "passive"))
    )
    (net (code "14") (name "DIO_RESET") (class "Default")
      (node (ref "CON3") (pin "27") (pinfunction "27_27") (pintype "bidirectional"))
      (node (ref "MODULE_DIO") (pin "A12") (pinfunction "12_A12") (pintype "passive"))
    )
    (net (code "15") (name "DPHY0_C_N") (class "Default")
      (node (ref "J3") (pin "8") (pinfunction "8_8") (pintype "passive"))
      (node (ref "PI1") (pin "128") (pinfunction "28_128") (pintype "passive"))
    )
    (net (code "16") (name "DPHY0_C_P") (class "Default")
      (node (ref "J3") (pin "9") (pinfunction "9_9") (pintype "passive"))
      (node (ref "PI1") (pin "130") (pinfunction "30_130") (pintype "passive"))
    )
    (net (code "17") (name "DPHY0_D0_N") (class "Default")
      (node (ref "J3") (pin "2") (pinfunction "2_2") (pintype "passive"))
      (node (ref "PI1") (pin "116") (pinfunction "16_116") (pintype "passive"))
    )
    (net (code "18") (name "DPHY0_D0_P") (class "Default")
      (node (ref "J3") (pin "3") (pinfunction "3_3") (pintype "passive"))
      (node (ref "PI1") (pin "118") (pinfunction "18_118") (pintype "passive"))
    )
    (net (code "19") (name "DPHY0_D1_N") (class "Default")
      (node (ref "J3") (pin "5") (pinfunction "5_5") (pintype "passive"))
      (node (ref "PI1") (pin "122") (pinfunction "22_122") (pintype "passive"))
    )
    (net (code "20") (name "DPHY0_D1_P") (class "Default")
      (node (ref "J3") (pin "6") (pinfunction "6_6") (pintype "passive"))
      (node (ref "PI1") (pin "124") (pinfunction "24_124") (pintype "passive"))
    )
    (net (code "21") (name "DPHY0_D2_N") (class "Default")
      (node (ref "J3") (pin "11") (pinfunction "11_11") (pintype "passive"))
      (node (ref "PI1") (pin "134") (pinfunction "34_134") (pintype "passive"))
    )
    (net (code "22") (name "DPHY0_D2_P") (class "Default")
      (node (ref "J3") (pin "12") (pinfunction "12_12") (pintype "passive"))
      (node (ref "PI1") (pin "136") (pinfunction "36_136") (pintype "passive"))
    )
    (net (code "23") (name "DPHY0_D3_N") (class "Default")
      (node (ref "J3") (pin "14") (pinfunction "14_14") (pintype "passive"))
      (node (ref "PI1") (pin "140") (pinfunction "40_140") (pintype "passive"))
    )
    (net (code "24") (name "DPHY0_D3_P") (class "Default")
      (node (ref "J3") (pin "15") (pinfunction "15_15") (pintype "passive"))
      (node (ref "PI1") (pin "142") (pinfunction "42_142") (pintype "passive"))
    )
    (net (code "25") (name "DPHY1_C_N") (class "Default")
      (node (ref "J4") (pin "8") (pinfunction "8_8") (pintype "passive"))
      (node (ref "PI1") (pin "188") (pinfunction "88_188") (pintype "passive"))
    )
    (net (code "26") (name "DPHY1_C_P") (class "Default")
      (node (ref "J4") (pin "9") (pinfunction "9_9") (pintype "passive"))
      (node (ref "PI1") (pin "190") (pinfunction "90_190") (pintype "passive"))
    )
    (net (code "27") (name "DPHY1_D0_N") (class "Default")
      (node (ref "J4") (pin "2") (pinfunction "2_2") (pintype "passive"))
      (node (ref "PI1") (pin "176") (pinfunction "76_176") (pintype "passive"))
    )
    (net (code "28") (name "DPHY1_D0_P") (class "Default")
      (node (ref "J4") (pin "3") (pinfunction "3_3") (pintype "passive"))
      (node (ref "PI1") (pin "178") (pinfunction "78_178") (pintype "passive"))
    )
    (net (code "29") (name "DPHY1_D1_N") (class "Default")
      (node (ref "J4") (pin "5") (pinfunction "5_5") (pintype "passive"))
      (node (ref "PI1") (pin "182") (pinfunction "82_182") (pintype "passive"))
    )
    (net (code "30") (name "DPHY1_D1_P") (class "Default")
      (node (ref "J4") (pin "6") (pinfunction "6_6") (pintype "passive"))
      (node (ref "PI1") (pin "184") (pinfunction "84_184") (pintype "passive"))
    )
    (net (code "31") (name "DPHY1_D2_N") (class "Default")
      (node (ref "J4") (pin "11") (pinfunction "11_11") (pintype "passive"))
      (node (ref "PI1") (pin "194") (pinfunction "94_194") (pintype "passive"))
    )
    (net (code "32") (name "DPHY1_D2_P") (class "Default")
      (node (ref "J4") (pin "12") (pinfunction "12_12") (pintype "passive"))
      (node (ref "PI1") (pin "196") (pinfunction "96_196") (pintype "passive"))
    )
    (net (code "33") (name "DPHY1_D3_N") (class "Default")
      (node (ref "J4") (pin "14") (pinfunction "14_14") (pintype "passive"))
      (node (ref "PI1") (pin "193") (pinfunction "93_193") (pintype "passive"))
    )
    (net (code "34") (name "DPHY1_D3_P") (class "Default")
      (node (ref "J4") (pin "15") (pinfunction "15_15") (pintype "passive"))
      (node (ref "PI1") (pin "195") (pinfunction "95_195") (pintype "passive"))
    )
    (net (code "35") (name "EEPROM_NWP") (class "Default")
      (node (ref "JP2") (pin "4") (pinfunction "4_4") (pintype "bidirectional"))
      (node (ref "PI1") (pin "19") (pinfunction "19_19") (pintype "passive"))
    )
    (net (code "36") (name "ETH_LEDG") (class "Default")
      (node (ref "PI1") (pin "18") (pinfunction "18_18") (pintype "passive"))
      (node (ref "R8") (pin "1") (pinfunction "1_1") (pintype "passive"))
    )
    (net (code "37") (name "ETH_LEDY") (class "Default")
      (node (ref "PI1") (pin "16") (pinfunction "16_16") (pintype "passive"))
      (node (ref "R9") (pin "2") (pinfunction "2_2") (pintype "passive"))
    )
    (net (code "38") (name "GND") (class "Default")
      (node (ref "2230") (pin "1") (pinfunction "1_1") (pintype "passive"))
      (node (ref "2242") (pin "1") (pinfunction "1_1") (pintype "passive"))
      (node (ref "2260") (pin "1") (pinfunction "1_1") (pintype "passive"))
      (node (ref "2280") (pin "1") (pinfunction "1_1") (pintype "passive"))
      (node (ref "C1") (pin "2") (pinfunction "2_2") (pintype "passive"))
      (node (ref "C10") (pin "2") (pinfunction "2_2") (pintype "passive"))
      (node (ref "C11") (pin "2") (pinfunction "2_2") (pintype "passive"))
      (node (ref "C12") (pin "2") (pinfunction "2_2") (pintype "passive"))
      (node (ref "C14") (pin "2") (pinfunction "2_2") (pintype "passive"))
      (node (ref "C15") (pin "2") (pinfunction "2_2") (pintype "passive"))
      (node (ref "C16") (pin "2") (pinfunction "2_2") (pintype "passive"))
      (node (ref "C17") (pin "2") (pinfunction "2_2") (pintype "passive"))
      (node (ref "C18") (pin "2") (pinfunction "2_2") (pintype "passive"))
      (node (ref "C19") (pin "2") (pinfunction "2_2") (pintype "passive"))
      (node (ref "C2") (pin "2") (pinfunction "2_2") (pintype "passive"))
      (node (ref "C20") (pin "2") (pinfunction "2_2") (pintype "passive"))
      (node (ref "C21") (pin "2") (pinfunction "2_2") (pintype "passive"))
      (node (ref "C3") (pin "2") (pinfunction "2_2") (pintype "passive"))
      (node (ref "C4") (pin "2") (pinfunction "2_2") (pintype "passive"))
      (node (ref "C5") (pin "2") (pinfunction "2_2") (pintype "passive"))
      (node (ref "C6") (pin "2") (pinfunction "2_2") (pintype "passive"))
      (node (ref "C7") (pin "2") (pinfunction "2_2") (pintype "passive"))
      (node (ref "C8") (pin "2") (pinfunction "2_2") (pintype "passive"))
      (node (ref "C9") (pin "2") (pinfunction "2_2") (pintype "passive"))
      (node (ref "D1") (pin "3") (pinfunction "GND_3") (pintype "bidirectional"))
      (node (ref "D1") (pin "8") (pinfunction "GND_8") (pintype "bidirectional"))
      (node (ref "D2") (pin "3") (pinfunction "GND_3") (pintype "bidirectional"))
      (node (ref "D2") (pin "8") (pinfunction "GND_8") (pintype "bidirectional"))
      (node (ref "ETH1") (pin "MH3") (pinfunction "SHIELD_MH3") (pintype "bidirectional"))
      (node (ref "ETH1") (pin "MH4") (pinfunction "SHIELD_MH4") (pintype "bidirectional"))
      (node (ref "FAN") (pin "2") (pinfunction "P$2_2") (pintype "bidirectional"))
      (node (ref "GPIO") (pin "14") (pinfunction "14_14") (pintype "bidirectional"))
      (node (ref "GPIO") (pin "20") (pinfunction "20_20") (pintype "bidirectional"))
      (node (ref "GPIO") (pin "25") (pinfunction "25_25") (pintype "bidirectional"))
      (node (ref "GPIO") (pin "30") (pinfunction "30_30") (pintype "bidirectional"))
      (node (ref "GPIO") (pin "34") (pinfunction "34_34") (pintype "bidirectional"))
      (node (ref "GPIO") (pin "39") (pinfunction "39_39") (pintype "bidirectional"))
      (node (ref "GPIO") (pin "6") (pinfunction "6_6") (pintype "bidirectional"))
      (node (ref "GPIO") (pin "9") (pinfunction "9_9") (pintype "bidirectional"))
      (node (ref "HDMI1") (pin "11") (pinfunction "TMDSCLOCK+_11") (pintype "passive"))
      (node (ref "HDMI1") (pin "17") (pinfunction "UTILITY/HEAC+_17") (pintype "passive"))
      (node (ref "HDMI1") (pin "2") (pinfunction "TMDS2+_2") (pintype "passive"))
      (node (ref "HDMI1") (pin "5") (pinfunction "TMDSDATA1+_5") (pintype "passive"))
      (node (ref "HDMI1") (pin "8") (pinfunction "TMDS0+_8") (pintype "passive"))
      (node (ref "HDMI1") (pin "S1") (pinfunction "SHIELD_S1") (pintype "passive"))
      (node (ref "HDMI1") (pin "S2") (pinfunction "SHIELD_S2") (pintype "passive"))
      (node (ref "HDMI1") (pin "S3") (pinfunction "SHIELD_S3") (pintype "passive"))
      (node (ref "HDMI1") (pin "S4") (pinfunction "SHIELD_S4") (pintype "passive"))
      (node (ref "HDMI2") (pin "11") (pinfunction "TMDSCLOCK+_11") (pintype "passive"))
      (node (ref "HDMI2") (pin "17") (pinfunction "UTILITY/HEAC+_17") (pintype "passive"))
      (node (ref "HDMI2") (pin "2") (pinfunction "TMDS2+_2") (pintype "passive"))
      (node (ref "HDMI2") (pin "5") (pinfunction "TMDSDATA1+_5") (pintype "passive"))
      (node (ref "HDMI2") (pin "8") (pinfunction "TMDS0+_8") (pintype "passive"))
      (node (ref "HDMI2") (pin "S1") (pinfunction "SHIELD_S1") (pintype "passive"))
      (node (ref "HDMI2") (pin "S2") (pinfunction "SHIELD_S2") (pintype "passive"))
      (node (ref "HDMI2") (pin "S3") (pinfunction "SHIELD_S3") (pintype "passive"))
      (node (ref "HDMI2") (pin "S4") (pinfunction "SHIELD_S4") (pintype "passive"))
      (node (ref "IC1") (pin "2") (pinfunction "GND_2") (pintype "power_in"))
      (node (ref "IC2") (pin "2") (pinfunction "GND_2") (pintype "bidirectional"))
      (node (ref "IC3") (pin "3") (pinfunction "GND_3") (pintype "bidirectional"))
      (node (ref "IC4") (pin "3") (pinfunction "GND_3") (pintype "power_in"))
      (node (ref "IC5") (pin "4") (pinfunction "PGND_4") (pintype "power_in"))
      (node (ref "IC5") (pin "8") (pinfunction "SGND_8") (pintype "power_in"))
      (node (ref "IC5") (pin "9") (pinfunction "PGND_9") (pintype "power_in"))
      (node (ref "J1") (pin "4") (pinfunction "GND_4") (pintype "passive"))
      (node (ref "J1") (pin "7") (pinfunction "GND_DRAIN_7") (pintype "passive"))
      (node (ref "J1") (pin "S1") (pinfunction "SHIELD_S1") (pintype "passive"))
      (node (ref "J1") (pin "S2") (pinfunction "SHIELD_S2") (pintype "passive"))
      (node (ref "J2") (pin "4") (pinfunction "GND_4") (pintype "passive"))
      (node (ref "J2") (pin "7") (pinfunction "GND_DRAIN_7") (pintype "passive"))
      (node (ref "J2") (pin "S1") (pinfunction "SHIELD_S1") (pintype "passive"))
      (node (ref "J2") (pin "S2") (pinfunction "SHIELD_S2") (pintype "passive"))
      (node (ref "J3") (pin "1") (pinfunction "1_1") (pintype "passive"))
      (node (ref "J3") (pin "10") (pinfunction "10_10") (pintype "passive"))
      (node (ref "J3") (pin "13") (pinfunction "13_13") (pintype "passive"))
      (node (ref "J3") (pin "16") (pinfunction "16_16") (pintype "passive"))
      (node (ref "J3") (pin "19") (pinfunction "19_19") (pintype "passive"))
      (node (ref "J3") (pin "23") (pinfunction "MH1_23") (pintype "passive"))
      (node (ref "J3") (pin "24") (pinfunction "MH2_24") (pintype "passive"))
      (node (ref "J3") (pin "25") (pinfunction "MH1_25") (pintype "passive"))
      (node (ref "J3") (pin "26") (pinfunction "MH2_26") (pintype "passive"))
      (node (ref "J3") (pin "4") (pinfunction "4_4") (pintype "passive"))
      (node (ref "J3") (pin "7") (pinfunction "7_7") (pintype "passive"))
      (node (ref "J4") (pin "1") (pinfunction "1_1") (pintype "passive"))
      (node (ref "J4") (pin "10") (pinfunction "10_10") (pintype "passive"))
      (node (ref "J4") (pin "13") (pinfunction "13_13") (pintype "passive"))
      (node (ref "J4") (pin "16") (pinfunction "16_16") (pintype "passive"))
      (node (ref "J4") (pin "19") (pinfunction "19_19") (pintype "passive"))
      (node (ref "J4") (pin "23") (pinfunction "MH1_23") (pintype "passive"))
      (node (ref "J4") (pin "24") (pinfunction "MH2_24") (pintype "passive"))
      (node (ref "J4") (pin "25") (pinfunction "MH1_25") (pintype "passive"))
      (node (ref "J4") (pin "26") (pinfunction "MH2_26") (pintype "passive"))
      (node (ref "J4") (pin "4") (pinfunction "4_4") (pintype "passive"))
      (node (ref "J4") (pin "7") (pinfunction "7_7") (pintype "passive"))
      (node (ref "JP2") (pin "1") (pinfunction "1_1") (pintype "bidirectional"))
      (node (ref "JP2") (pin "11") (pinfunction "11_11") (pintype "bidirectional"))
      (node (ref "JP2") (pin "13") (pinfunction "13_13") (pintype "bidirectional"))
      (node (ref "JP2") (pin "3") (pinfunction "3_3") (pintype "bidirectional"))
      (node (ref "JP2") (pin "5") (pinfunction "5_5") (pintype "bidirectional"))
      (node (ref "JP2") (pin "7") (pinfunction "7_7") (pintype "bidirectional"))
      (node (ref "JP2") (pin "9") (pinfunction "9_9") (pintype "bidirectional"))
      (node (ref "JP3") (pin "2") (pinfunction "2_2") (pintype "bidirectional"))
      (node (ref "JP3") (pin "4") (pinfunction "4_4") (pintype "bidirectional"))
      (node (ref "MODULE_AIO") (pin "A10") (pinfunction "10_A10") (pintype "passive"))
      (node (ref "MODULE_AIO") (pin "A14") (pinfunction "14_A14") (pintype "passive"))
      (node (ref "MODULE_AIO") (pin "A15") (pinfunction "15_A15") (pintype "passive"))
      (node (ref "MODULE_AIO") (pin "A16") (pinfunction "16_A16") (pintype "passive"))
      (node (ref "MODULE_AIO") (pin "A25") (pinfunction "25_A25") (pintype "passive"))
      (node (ref "MODULE_AIO") (pin "A30") (pinfunction "30_A30") (pintype "passive"))
      (node (ref "MODULE_AIO") (pin "A31") (pinfunction "31_A31") (pintype "passive"))
      (node (ref "MODULE_AIO") (pin "A32") (pinfunction "32_A32") (pintype "passive"))
      (node (ref "MODULE_AIO") (pin "B10") (pinfunction "10_B10") (pintype "passive"))
      (node (ref "MODULE_AIO") (pin "B14") (pinfunction "14_B14") (pintype "passive"))
      (node (ref "MODULE_AIO") (pin "B15") (pinfunction "15_B15") (pintype "passive"))
      (node (ref "MODULE_AIO") (pin "B16") (pinfunction "16_B16") (pintype "passive"))
      (node (ref "MODULE_AIO") (pin "B19") (pinfunction "19_B19") (pintype "passive"))
      (node (ref "MODULE_AIO") (pin "B22") (pinfunction "22_B22") (pintype "passive"))
      (node (ref "MODULE_AIO") (pin "B25") (pinfunction "25_B25") (pintype "passive"))
      (node (ref "MODULE_AIO") (pin "B30") (pinfunction "30_B30") (pintype "passive"))
      (node (ref "MODULE_AIO") (pin "B31") (pinfunction "31_B31") (pintype "passive"))
      (node (ref "MODULE_AIO") (pin "B32") (pinfunction "32_B32") (pintype "passive"))
      (node (ref "MODULE_DIO") (pin "A10") (pinfunction "10_A10") (pintype "passive"))
      (node (ref "MODULE_DIO") (pin "A14") (pinfunction "14_A14") (pintype "passive"))
      (node (ref "MODULE_DIO") (pin "A15") (pinfunction "15_A15") (pintype "passive"))
      (node (ref "MODULE_DIO") (pin "A16") (pinfunction "16_A16") (pintype "passive"))
      (node (ref "MODULE_DIO") (pin "A25") (pinfunction "25_A25") (pintype "passive"))
      (node (ref "MODULE_DIO") (pin "A30") (pinfunction "30_A30") (pintype "passive"))
      (node (ref "MODULE_DIO") (pin "A31") (pinfunction "31_A31") (pintype "passive"))
      (node (ref "MODULE_DIO") (pin "A32") (pinfunction "32_A32") (pintype "passive"))
      (node (ref "MODULE_DIO") (pin "B10") (pinfunction "10_B10") (pintype "passive"))
      (node (ref "MODULE_DIO") (pin "B14") (pinfunction "14_B14") (pintype "passive"))
      (node (ref "MODULE_DIO") (pin "B15") (pinfunction "15_B15") (pintype "passive"))
      (node (ref "MODULE_DIO") (pin "B16") (pinfunction "16_B16") (pintype "passive"))
      (node (ref "MODULE_DIO") (pin "B19") (pinfunction "19_B19") (pintype "passive"))
      (node (ref "MODULE_DIO") (pin "B22") (pinfunction "22_B22") (pintype "passive"))
      (node (ref "MODULE_DIO") (pin "B25") (pinfunction "25_B25") (pintype "passive"))
      (node (ref "MODULE_DIO") (pin "B30") (pinfunction "30_B30") (pintype "passive"))
      (node (ref "MODULE_DIO") (pin "B31") (pinfunction "31_B31") (pintype "passive"))
      (node (ref "MODULE_DIO") (pin "B32") (pinfunction "32_B32") (pintype "passive"))
      (node (ref "PCIE") (pin "1") (pinfunction "GND1_1") (pintype "bidirectional"))
      (node (ref "PCIE") (pin "15") (pinfunction "GND4_15") (pintype "bidirectional"))
      (node (ref "PCIE") (pin "21") (pinfunction "GND5_21") (pintype "bidirectional"))
      (node (ref "PCIE") (pin "27") (pinfunction "GND6_27") (pintype "bidirectional"))
      (node (ref "PCIE") (pin "3") (pinfunction "GND2_3") (pintype "bidirectional"))
      (node (ref "PCIE") (pin "33") (pinfunction "GND7_33") (pintype "bidirectional"))
      (node (ref "PCIE") (pin "39") (pinfunction "GND8_39") (pintype "bidirectional"))
      (node (ref "PCIE") (pin "45") (pinfunction "GND9_45") (pintype "bidirectional"))
      (node (ref "PCIE") (pin "51") (pinfunction "GND10_51") (pintype "bidirectional"))
      (node (ref "PCIE") (pin "57") (pinfunction "GND11_57") (pintype "bidirectional"))
      (node (ref "PCIE") (pin "71") (pinfunction "GND12_71") (pintype "bidirectional"))
      (node (ref "PCIE") (pin "73") (pinfunction "GND13_73") (pintype "bidirectional"))
      (node (ref "PCIE") (pin "75") (pinfunction "GND14_75") (pintype "bidirectional"))
      (node (ref "PCIE") (pin "9") (pinfunction "GND3_9") (pintype "bidirectional"))
      (node (ref "PCIE") (pin "S1") (pinfunction "S1_S1") (pintype "bidirectional"))
      (node (ref "PCIE") (pin "S2") (pinfunction "S2_S2") (pintype "bidirectional"))
      (node (ref "PI1") (pin "1") (pinfunction "1_1") (pintype "passive"))
      (node (ref "PI1") (pin "107") (pinfunction "7_107") (pintype "passive"))
      (node (ref "PI1") (pin "108") (pinfunction "8_108") (pintype "passive"))
      (node (ref "PI1") (pin "113") (pinfunction "13_113") (pintype "passive"))
      (node (ref "PI1") (pin "114") (pinfunction "14_114") (pintype "passive"))
      (node (ref "PI1") (pin "119") (pinfunction "19_119") (pintype "passive"))
      (node (ref "PI1") (pin "120") (pinfunction "20_120") (pintype "passive"))
      (node (ref "PI1") (pin "125") (pinfunction "25_125") (pintype "passive"))
      (node (ref "PI1") (pin "126") (pinfunction "26_126") (pintype "passive"))
      (node (ref "PI1") (pin "13") (pinfunction "13_13") (pintype "passive"))
      (node (ref "PI1") (pin "131") (pinfunction "31_131") (pintype "passive"))
      (node (ref "PI1") (pin "132") (pinfunction "32_132") (pintype "passive"))
      (node (ref "PI1") (pin "137") (pinfunction "37_137") (pintype "passive"))
      (node (ref "PI1") (pin "138") (pinfunction "38_138") (pintype "passive"))
      (node (ref "PI1") (pin "14") (pinfunction "14_14") (pintype "passive"))
      (node (ref "PI1") (pin "143") (pinfunction "43_143") (pintype "passive"))
      (node (ref "PI1") (pin "149") (pinfunction "49_149") (pintype "passive"))
      (node (ref "PI1") (pin "155") (pinfunction "55_155") (pintype "passive"))
      (node (ref "PI1") (pin "156") (pinfunction "56_156") (pintype "passive"))
      (node (ref "PI1") (pin "161") (pinfunction "61_161") (pintype "passive"))
      (node (ref "PI1") (pin "162") (pinfunction "62_162") (pintype "passive"))
      (node (ref "PI1") (pin "167") (pinfunction "67_167") (pintype "passive"))
      (node (ref "PI1") (pin "168") (pinfunction "68_168") (pintype "passive"))
      (node (ref "PI1") (pin "173") (pinfunction "73_173") (pintype "passive"))
      (node (ref "PI1") (pin "174") (pinfunction "74_174") (pintype "passive"))
      (node (ref "PI1") (pin "179") (pinfunction "79_179") (pintype "passive"))
      (node (ref "PI1") (pin "180") (pinfunction "80_180") (pintype "passive"))
      (node (ref "PI1") (pin "185") (pinfunction "85_185") (pintype "passive"))
      (node (ref "PI1") (pin "186") (pinfunction "86_186") (pintype "passive"))
      (node (ref "PI1") (pin "191") (pinfunction "91_191") (pintype "passive"))
      (node (ref "PI1") (pin "192") (pinfunction "92_192") (pintype "passive"))
      (node (ref "PI1") (pin "197") (pinfunction "97_197") (pintype "passive"))
      (node (ref "PI1") (pin "198") (pinfunction "98_198") (pintype "passive"))
      (node (ref "PI1") (pin "2") (pinfunction "2_2") (pintype "passive"))
      (node (ref "PI1") (pin "21") (pinfunction "21_21") (pintype "passive"))
      (node (ref "PI1") (pin "24") (pinfunction "24_24") (pintype "passive"))
      (node (ref "PI1") (pin "31") (pinfunction "31_31") (pintype "passive"))
      (node (ref "PI1") (pin "34") (pinfunction "34_34") (pintype "passive"))
      (node (ref "PI1") (pin "41") (pinfunction "41_41") (pintype "passive"))
      (node (ref "PI1") (pin "44") (pinfunction "44_44") (pintype "passive"))
      (node (ref "PI1") (pin "51") (pinfunction "51_51") (pintype "passive"))
      (node (ref "PI1") (pin "54") (pinfunction "54_54") (pintype "passive"))
      (node (ref "PI1") (pin "59") (pinfunction "59_59") (pintype "passive"))
      (node (ref "PI1") (pin "60") (pinfunction "60_60") (pintype "passive"))
      (node (ref "PI1") (pin "65") (pinfunction "65_65") (pintype "passive"))
      (node (ref "PI1") (pin "66") (pinfunction "66_66") (pintype "passive"))
      (node (ref "PI1") (pin "7") (pinfunction "7_7") (pintype "passive"))
      (node (ref "PI1") (pin "72") (pinfunction "72_72") (pintype "passive"))
      (node (ref "PI1") (pin "73") (pinfunction "73_73") (pintype "passive"))
      (node (ref "PI1") (pin "8") (pinfunction "8_8") (pintype "passive"))
      (node (ref "PI1") (pin "97") (pinfunction "97_97") (pintype "passive"))
      (node (ref "R1") (pin "2") (pinfunction "2_2") (pintype "passive"))
      (node (ref "R11") (pin "2") (pinfunction "2_2") (pintype "passive"))
      (node (ref "R13") (pin "2") (pinfunction "2_2") (pintype "passive"))
      (node (ref "R2") (pin "2") (pinfunction "2_2") (pintype "passive"))
      (node (ref "SD1") (pin "MT1") (pinfunction "MT1_MT1") (pintype "bidirectional"))
      (node (ref "SD1") (pin "MT2") (pinfunction "MT2_MT2") (pintype "bidirectional"))
      (node (ref "SD1") (pin "MT3") (pinfunction "MT3_MT3") (pintype "bidirectional"))
      (node (ref "SD1") (pin "MT4") (pinfunction "MT4_MT4") (pintype "bidirectional"))
      (node (ref "SD1") (pin "VSS") (pinfunction "VSS_VSS") (pintype "bidirectional"))
      (node (ref "SW1") (pin "1") (pinfunction "1_1") (pintype "passive"))
      (node (ref "SW1") (pin "3") (pinfunction "3_3") (pintype "passive"))
      (node (ref "SW1") (pin "4") (pinfunction "4_4") (pintype "passive"))
      (node (ref "USBC") (pin "A1") (pinfunction "GND_A1") (pintype "passive"))
      (node (ref "USBC") (pin "A12") (pinfunction "GND1_A12") (pintype "passive"))
      (node (ref "USBC") (pin "B1") (pinfunction "GND3_B1") (pintype "passive"))
      (node (ref "USBC") (pin "B12") (pinfunction "GND2_B12") (pintype "passive"))
      (node (ref "USBC") (pin "S1") (pinfunction "SHIELD_S1") (pintype "passive"))
      (node (ref "USBC") (pin "S2") (pinfunction "SHIELD_S2") (pintype "passive"))
      (node (ref "USBC") (pin "S3") (pinfunction "SHIELD_S3") (pintype "passive"))
      (node (ref "USBC") (pin "S4") (pinfunction "SHIELD_S4") (pintype "passive"))
      (node (ref "X2") (pin "2") (pinfunction "VSS_2") (pintype "power_in"))
    )
    (net (code "39") (name "GPIO2") (class "Default")
      (node (ref "CON3") (pin "24") (pinfunction "24_24") (pintype "bidirectional"))
      (node (ref "GPIO") (pin "3") (pinfunction "3_3") (pintype "bidirectional"))
      (node (ref "PI1") (pin "57") (pinfunction "57_57") (pintype "passive"))
    )
    (net (code "40") (name "GPIO3") (class "Default")
      (node (ref "CON3") (pin "22") (pinfunction "22_22") (pintype "bidirectional"))
      (node (ref "GPIO") (pin "5") (pinfunction "5_5") (pintype "bidirectional"))
      (node (ref "PI1") (pin "55") (pinfunction "55_55") (pintype "passive"))
    )
    (net (code "41") (name "GPIO4") (class "Default")
      (node (ref "CON2") (pin "28") (pinfunction "28_28") (pintype "bidirectional"))
      (node (ref "GPIO") (pin "7") (pinfunction "7_7") (pintype "bidirectional"))
      (node (ref "PI1") (pin "53") (pinfunction "53_53") (pintype "passive"))
    )
    (net (code "42") (name "GPIO5") (class "Default")
      (node (ref "CON2") (pin "22") (pinfunction "22_22") (pintype "bidirectional"))
      (node (ref "GPIO") (pin "29") (pinfunction "29_29") (pintype "bidirectional"))
      (node (ref "PI1") (pin "33") (pinfunction "33_33") (pintype "passive"))
    )
    (net (code "43") (name "GPIO6") (class "Default")
      (node (ref "CON2") (pin "26") (pinfunction "26_26") (pintype "bidirectional"))
      (node (ref "CON3") (pin "30") (pinfunction "30_30") (pintype "bidirectional"))
      (node (ref "GPIO") (pin "31") (pinfunction "31_31") (pintype "bidirectional"))
      (node (ref "PI1") (pin "29") (pinfunction "29_29") (pintype "passive"))
    )
    (net (code "44") (name "GPIO7") (class "Default")
      (node (ref "CON3") (pin "4") (pinfunction "4_4") (pintype "bidirectional"))
      (node (ref "GPIO") (pin "26") (pinfunction "26_26") (pintype "bidirectional"))
      (node (ref "PI1") (pin "38") (pinfunction "38_38") (pintype "passive"))
    )
    (net (code "45") (name "GPIO8") (class "Default")
      (node (ref "CON3") (pin "6") (pinfunction "6_6") (pintype "bidirectional"))
      (node (ref "GPIO") (pin "24") (pinfunction "24_24") (pintype "bidirectional"))
      (node (ref "PI1") (pin "40") (pinfunction "40_40") (pintype "passive"))
    )
    (net (code "46") (name "GPIO9") (class "Default")
      (node (ref "CON3") (pin "12") (pinfunction "12_12") (pintype "bidirectional"))
      (node (ref "GPIO") (pin "21") (pinfunction "21_21") (pintype "bidirectional"))
      (node (ref "PI1") (pin "39") (pinfunction "39_39") (pintype "passive"))
    )
    (net (code "47") (name "GPIO10") (class "Default")
      (node (ref "CON3") (pin "10") (pinfunction "10_10") (pintype "bidirectional"))
      (node (ref "GPIO") (pin "19") (pinfunction "19_19") (pintype "bidirectional"))
      (node (ref "PI1") (pin "43") (pinfunction "43_43") (pintype "passive"))
    )
    (net (code "48") (name "GPIO11") (class "Default")
      (node (ref "CON3") (pin "8") (pinfunction "8_8") (pintype "bidirectional"))
      (node (ref "GPIO") (pin "23") (pinfunction "23_23") (pintype "bidirectional"))
      (node (ref "PI1") (pin "37") (pinfunction "37_37") (pintype "passive"))
    )
    (net (code "49") (name "GPIO12") (class "Default")
      (node (ref "CON2") (pin "18") (pinfunction "18_18") (pintype "bidirectional"))
      (node (ref "GPIO") (pin "32") (pinfunction "32_32") (pintype "bidirectional"))
      (node (ref "PI1") (pin "32") (pinfunction "32_32") (pintype "passive"))
    )
    (net (code "50") (name "GPIO13") (class "Default")
      (node (ref "CON2") (pin "24") (pinfunction "24_24") (pintype "bidirectional"))
      (node (ref "GPIO") (pin "33") (pinfunction "33_33") (pintype "bidirectional"))
      (node (ref "PI1") (pin "27") (pinfunction "27_27") (pintype "passive"))
    )
    (net (code "51") (name "GPIO14") (class "Default")
      (node (ref "CON3") (pin "18") (pinfunction "18_18") (pintype "bidirectional"))
      (node (ref "GPIO") (pin "8") (pinfunction "8_8") (pintype "bidirectional"))
      (node (ref "PI1") (pin "56") (pinfunction "56_56") (pintype "passive"))
    )
    (net (code "52") (name "GPIO15") (class "Default")
      (node (ref "CON3") (pin "20") (pinfunction "20_20") (pintype "bidirectional"))
      (node (ref "GPIO") (pin "10") (pinfunction "10_10") (pintype "bidirectional"))
      (node (ref "PI1") (pin "52") (pinfunction "52_52") (pintype "passive"))
    )
    (net (code "53") (name "GPIO16") (class "Default")
      (node (ref "CON2") (pin "36") (pinfunction "36_36") (pintype "bidirectional"))
      (node (ref "GPIO") (pin "36") (pinfunction "36_36") (pintype "bidirectional"))
      (node (ref "PI1") (pin "30") (pinfunction "30_30") (pintype "passive"))
    )
    (net (code "54") (name "GPIO17") (class "Default")
      (node (ref "CON2") (pin "38") (pinfunction "38_38") (pintype "bidirectional"))
      (node (ref "GPIO") (pin "11") (pinfunction "11_11") (pintype "bidirectional"))
      (node (ref "PI1") (pin "49") (pinfunction "49_49") (pintype "passive"))
    )
    (net (code "55") (name "GPIO18") (class "Default")
      (node (ref "CON2") (pin "40") (pinfunction "40_40") (pintype "bidirectional"))
      (node (ref "GPIO") (pin "12") (pinfunction "12_12") (pintype "bidirectional"))
      (node (ref "PI1") (pin "50") (pinfunction "50_50") (pintype "passive"))
    )
    (net (code "56") (name "GPIO19") (class "Default")
      (node (ref "CON2") (pin "30") (pinfunction "30_30") (pintype "bidirectional"))
      (node (ref "GPIO") (pin "35") (pinfunction "35_35") (pintype "bidirectional"))
      (node (ref "PI1") (pin "25") (pinfunction "25_25") (pintype "passive"))
    )
    (net (code "57") (name "GPIO20") (class "Default")
      (node (ref "CON2") (pin "32") (pinfunction "32_32") (pintype "bidirectional"))
      (node (ref "GPIO") (pin "38") (pinfunction "38_38") (pintype "bidirectional"))
      (node (ref "PI1") (pin "28") (pinfunction "28_28") (pintype "passive"))
    )
    (net (code "58") (name "GPIO21") (class "Default")
      (node (ref "CON2") (pin "34") (pinfunction "34_34") (pintype "bidirectional"))
      (node (ref "GPIO") (pin "40") (pinfunction "40_40") (pintype "bidirectional"))
      (node (ref "PI1") (pin "26") (pinfunction "26_26") (pintype "passive"))
    )
    (net (code "59") (name "GPIO22") (class "Default")
      (node (ref "CON3") (pin "32") (pinfunction "32_32") (pintype "bidirectional"))
      (node (ref "GPIO") (pin "15") (pinfunction "15_15") (pintype "bidirectional"))
      (node (ref "PI1") (pin "45") (pinfunction "45_45") (pintype "passive"))
    )
    (net (code "60") (name "GPIO23") (class "Default")
      (node (ref "GPIO") (pin "16") (pinfunction "16_16") (pintype "bidirectional"))
      (node (ref "PI1") (pin "48") (pinfunction "48_48") (pintype "passive"))
    )
    (net (code "61") (name "GPIO24") (class "Default")
      (node (ref "CON3") (pin "14") (pinfunction "14_14") (pintype "bidirectional"))
      (node (ref "GPIO") (pin "18") (pinfunction "18_18") (pintype "bidirectional"))
      (node (ref "PI1") (pin "46") (pinfunction "46_46") (pintype "passive"))
    )
    (net (code "62") (name "GPIO25") (class "Default")
      (node (ref "CON3") (pin "16") (pinfunction "16_16") (pintype "bidirectional"))
      (node (ref "GPIO") (pin "22") (pinfunction "22_22") (pintype "bidirectional"))
      (node (ref "PI1") (pin "42") (pinfunction "42_42") (pintype "passive"))
    )
    (net (code "63") (name "GPIO26") (class "Default")
      (node (ref "CON2") (pin "20") (pinfunction "20_20") (pintype "bidirectional"))
      (node (ref "GPIO") (pin "37") (pinfunction "37_37") (pintype "bidirectional"))
      (node (ref "PI1") (pin "23") (pinfunction "23_23") (pintype "passive"))
    )
    (net (code "64") (name "GPIO27") (class "Default")
      (node (ref "CON3") (pin "34") (pinfunction "34_34") (pintype "bidirectional"))
      (node (ref "GPIO") (pin "13") (pinfunction "13_13") (pintype "bidirectional"))
      (node (ref "PI1") (pin "47") (pinfunction "47_47") (pintype "passive"))
    )
    (net (code "65") (name "GPIO_VREF") (class "Default")
      (node (ref "PI1") (pin "77") (pinfunction "77_77") (pintype "passive"))
      (node (ref "R3") (pin "1") (pinfunction "1_1") (pintype "passive"))
      (node (ref "R4") (pin "1") (pinfunction "1_1") (pintype "passive"))
      (node (ref "R6") (pin "2") (pinfunction "2_2") (pintype "passive"))
      (node (ref "R7") (pin "2") (pinfunction "2_2") (pintype "passive"))
      (node (ref "TP-GREF") (pin "TP") (pinfunction "P$1_TP") (pintype "bidirectional"))
    )
    (net (code "66") (name "HDMI0_CEC") (class "Default")
      (node (ref "HDMI2") (pin "13") (pinfunction "GROUND_13") (pintype "passive"))
      (node (ref "PI1") (pin "152") (pinfunction "52_152") (pintype "passive"))
    )
    (net (code "67") (name "HDMI0_CK_N") (class "Default")
      (node (ref "HDMI2") (pin "12") (pinfunction "TMDSCLOCK-_12") (pintype "passive"))
      (node (ref "PI1") (pin "189") (pinfunction "89_189") (pintype "passive"))
    )
    (net (code "68") (name "HDMI0_CK_P") (class "Default")
      (node (ref "HDMI2") (pin "10") (pinfunction "TMDSCLOCKSHIELD_10") (pintype "passive"))
      (node (ref "PI1") (pin "187") (pinfunction "87_187") (pintype "passive"))
    )
    (net (code "69") (name "HDMI0_D0_N") (class "Default")
      (node (ref "HDMI2") (pin "9") (pinfunction "TMDS0-_9") (pintype "passive"))
      (node (ref "PI1") (pin "183") (pinfunction "83_183") (pintype "passive"))
    )
    (net (code "70") (name "HDMI0_D0_P") (class "Default")
      (node (ref "HDMI2") (pin "7") (pinfunction "TMDS0SHIELD_7") (pintype "passive"))
      (node (ref "PI1") (pin "181") (pinfunction "81_181") (pintype "passive"))
    )
    (net (code "71") (name "HDMI0_D1_N") (class "Default")
      (node (ref "HDMI2") (pin "6") (pinfunction "TMDS1-_6") (pintype "passive"))
      (node (ref "PI1") (pin "177") (pinfunction "77_177") (pintype "passive"))
    )
    (net (code "72") (name "HDMI0_D1_P") (class "Default")
      (node (ref "HDMI2") (pin "4") (pinfunction "TMDS1SHIELD_4") (pintype "passive"))
      (node (ref "PI1") (pin "175") (pinfunction "75_175") (pintype "passive"))
    )
    (net (code "73") (name "HDMI0_D2_N") (class "Default")
      (node (ref "HDMI2") (pin "3") (pinfunction "TMDS2-_3") (pintype "passive"))
      (node (ref "PI1") (pin "171") (pinfunction "71_171") (pintype "passive"))
    )
    (net (code "74") (name "HDMI0_D2_P") (class "Default")
      (node (ref "HDMI2") (pin "1") (pinfunction "TMDS2SHIELD_1") (pintype "passive"))
      (node (ref "PI1") (pin "169") (pinfunction "69_169") (pintype "passive"))
    )
    (net (code "75") (name "HDMI0_HOTPLUG") (class "Default")
      (node (ref "HDMI2") (pin "19") (pinfunction "HOTPLUG/HEC+_19") (pintype "passive"))
      (node (ref "PI1") (pin "154") (pinfunction "54_154") (pintype "passive"))
    )
    (net (code "76") (name "HDMI0_SCL") (class "Default")
      (node (ref "HDMI2") (pin "15") (pinfunction "SCL_15") (pintype "passive"))
      (node (ref "PI1") (pin "199") (pinfunction "99_199") (pintype "passive"))
    )
    (net (code "77") (name "HDMI0_SDA") (class "Default")
      (node (ref "HDMI2") (pin "16") (pinfunction "SDA_16") (pintype "passive"))
      (node (ref "PI1") (pin "200") (pinfunction "100_200") (pintype "passive"))
    )
    (net (code "78") (name "HDMI1_CEC") (class "Default")
      (node (ref "HDMI1") (pin "13") (pinfunction "GROUND_13") (pintype "passive"))
      (node (ref "PI1") (pin "150") (pinfunction "50_150") (pintype "passive"))
    )
    (net (code "79") (name "HDMI1_CK_N") (class "Default")
      (node (ref "HDMI1") (pin "12") (pinfunction "TMDSCLOCK-_12") (pintype "passive"))
      (node (ref "PI1") (pin "165") (pinfunction "65_165") (pintype "passive"))
    )
    (net (code "80") (name "HDMI1_CK_P") (class "Default")
      (node (ref "HDMI1") (pin "10") (pinfunction "TMDSCLOCKSHIELD_10") (pintype "passive"))
      (node (ref "PI1") (pin "163") (pinfunction "63_163") (pintype "passive"))
    )
    (net (code "81") (name "HDMI1_D0_N") (class "Default")
      (node (ref "HDMI1") (pin "9") (pinfunction "TMDS0-_9") (pintype "passive"))
      (node (ref "PI1") (pin "159") (pinfunction "59_159") (pintype "passive"))
    )
    (net (code "82") (name "HDMI1_D0_P") (class "Default")
      (node (ref "HDMI1") (pin "7") (pinfunction "TMDS0SHIELD_7") (pintype "passive"))
      (node (ref "PI1") (pin "157") (pinfunction "57_157") (pintype "passive"))
    )
    (net (code "83") (name "HDMI1_D1_N") (class "Default")
      (node (ref "HDMI1") (pin "6") (pinfunction "TMDS1-_6") (pintype "passive"))
      (node (ref "PI1") (pin "153") (pinfunction "53_153") (pintype "passive"))
    )
    (net (code "84") (name "HDMI1_D1_P") (class "Default")
      (node (ref "HDMI1") (pin "4") (pinfunction "TMDS1SHIELD_4") (pintype "passive"))
      (node (ref "PI1") (pin "151") (pinfunction "51_151") (pintype "passive"))
    )
    (net (code "85") (name "HDMI1_D2_N") (class "Default")
      (node (ref "HDMI1") (pin "3") (pinfunction "TMDS2-_3") (pintype "passive"))
      (node (ref "PI1") (pin "147") (pinfunction "47_147") (pintype "passive"))
    )
    (net (code "86") (name "HDMI1_D2_P") (class "Default")
      (node (ref "HDMI1") (pin "1") (pinfunction "TMDS2SHIELD_1") (pintype "passive"))
      (node (ref "PI1") (pin "145") (pinfunction "45_145") (pintype "passive"))
    )
    (net (code "87") (name "HDMI1_HOTPLUG") (class "Default")
      (node (ref "HDMI1") (pin "19") (pinfunction "HOTPLUG/HEC+_19") (pintype "passive"))
      (node (ref "PI1") (pin "144") (pinfunction "44_144") (pintype "passive"))
    )
    (net (code "88") (name "HDMI1_SCL") (class "Default")
      (node (ref "HDMI1") (pin "15") (pinfunction "SCL_15") (pintype "passive"))
      (node (ref "PI1") (pin "148") (pinfunction "48_148") (pintype "passive"))
    )
    (net (code "89") (name "HDMI1_SDA") (class "Default")
      (node (ref "HDMI1") (pin "16") (pinfunction "SDA_16") (pintype "passive"))
      (node (ref "PI1") (pin "146") (pinfunction "46_146") (pintype "passive"))
    )
    (net (code "90") (name "HDMI_5V") (class "Default")
      (node (ref "C4") (pin "1") (pinfunction "1_1") (pintype "passive"))
      (node (ref "HDMI1") (pin "18") (pinfunction "POWER_18") (pintype "power_in"))
      (node (ref "HDMI2") (pin "18") (pinfunction "POWER_18") (pintype "power_in"))
      (node (ref "IC4") (pin "2") (pinfunction "OUT_2") (pintype "power_in"))
      (node (ref "TP-5VHD") (pin "TP") (pinfunction "P$1_TP") (pintype "bidirectional"))
    )
    (net (code "91") (name "ID_SC") (class "Default")
      (node (ref "GPIO") (pin "28") (pinfunction "28_28") (pintype "bidirectional"))
      (node (ref "ID") (pin "1") (pinfunction "1_1") (pintype "bidirectional"))
      (node (ref "PI1") (pin "36") (pinfunction "36_36") (pintype "passive"))
    )
    (net (code "92") (name "ID_SD") (class "Default")
      (node (ref "GPIO") (pin "27") (pinfunction "27_27") (pintype "bidirectional"))
      (node (ref "ID") (pin "3") (pinfunction "3_3") (pintype "bidirectional"))
      (node (ref "PI1") (pin "35") (pinfunction "35_35") (pintype "passive"))
    )
    (net (code "93") (name "LED_NACT") (class "Default")
      (node (ref "PI1") (pin "22") (pinfunction "22_22") (pintype "passive"))
    )
    (net (code "94") (name "M2_3V3") (class "Default")
      (node (ref "C12") (pin "1") (pinfunction "1_1") (pintype "passive"))
      (node (ref "C13") (pin "1") (pinfunction "1_1") (pintype "passive"))
      (node (ref "C14") (pin "1") (pinfunction "1_1") (pintype "passive"))
      (node (ref "C15") (pin "1") (pinfunction "1_1") (pintype "passive"))
      (node (ref "C16") (pin "1") (pinfunction "1_1") (pintype "passive"))
      (node (ref "C17") (pin "1") (pinfunction "1_1") (pintype "passive"))
      (node (ref "L1") (pin "2") (pinfunction "2_2") (pintype "passive"))
      (node (ref "PCIE") (pin "12") (pinfunction "VCC3_12") (pintype "bidirectional"))
      (node (ref "PCIE") (pin "14") (pinfunction "VCC4_14") (pintype "bidirectional"))
      (node (ref "PCIE") (pin "16") (pinfunction "VCC5_16") (pintype "bidirectional"))
      (node (ref "PCIE") (pin "18") (pinfunction "VCC6_18") (pintype "bidirectional"))
      (node (ref "PCIE") (pin "2") (pinfunction "VCC1_2") (pintype "bidirectional"))
      (node (ref "PCIE") (pin "4") (pinfunction "VCC2_4") (pintype "bidirectional"))
      (node (ref "PCIE") (pin "70") (pinfunction "VCC7_70") (pintype "bidirectional"))
      (node (ref "PCIE") (pin "72") (pinfunction "VCC8_72") (pintype "bidirectional"))
      (node (ref "PCIE") (pin "74") (pinfunction "VCC9_74") (pintype "bidirectional"))
      (node (ref "R12") (pin "1") (pinfunction "1_1") (pintype "passive"))
      (node (ref "TP-VM2") (pin "TP") (pinfunction "P$1_TP") (pintype "bidirectional"))
      (node (ref "X2") (pin "3") (pinfunction "OUT_3") (pintype "output"))
      (node (ref "X2") (pin "4") (pinfunction "VDD_4") (pintype "power_in"))
    )
    (net (code "95") (name "MISO_SEL") (class "Default")
      (node (ref "CON2") (pin "23") (pinfunction "23_23") (pintype "bidirectional"))
      (node (ref "MODULE_AIO") (pin "A13") (pinfunction "13_A13") (pintype "passive"))
    )
    (net (code "96") (name "NPWR_LED") (class "Default")
      (node (ref "IC3") (pin "2") (pinfunction "A_2") (pintype "input"))
      (node (ref "PI1") (pin "96") (pinfunction "96_96") (pintype "passive"))
      (node (ref "TP-LED") (pin "TP") (pinfunction "P$1_TP") (pintype "bidirectional"))
    )
    (net (code "97") (name "NRPIBOOT") (class "Default")
      (node (ref "JP2") (pin "2") (pinfunction "2_2") (pintype "bidirectional"))
      (node (ref "PI1") (pin "94") (pinfunction "94_94") (pintype "passive"))
    )
    (net (code "98") (name "Net-(C11-Pad1)") (class "Default")
      (node (ref "C11") (pin "1") (pinfunction "1_1") (pintype "passive"))
      (node (ref "ETH1") (pin "CT1") (pinfunction "CT1_CT1") (pintype "bidirectional"))
      (node (ref "ETH1") (pin "CT2") (pinfunction "CT2_CT2") (pintype "bidirectional"))
      (node (ref "ETH1") (pin "CT3") (pinfunction "CT3_CT3") (pintype "bidirectional"))
      (node (ref "ETH1") (pin "CT4") (pinfunction "CT4_CT4") (pintype "bidirectional"))
    )
    (net (code "99") (name "Net-(ETH1-P17)") (class "Default")
      (node (ref "ETH1") (pin "17") (pinfunction "P17_17") (pintype "bidirectional"))
      (node (ref "R9") (pin "1") (pinfunction "1_1") (pintype "passive"))
    )
    (net (code "100") (name "Net-(ETH1-P19)") (class "Default")
      (node (ref "ETH1") (pin "19") (pinfunction "P19_19") (pintype "bidirectional"))
      (node (ref "R8") (pin "2") (pinfunction "2_2") (pintype "passive"))
    )
    (net (code "101") (name "Net-(IC2-ILIM)") (class "Default")
      (node (ref "IC2") (pin "5") (pinfunction "ILIM_5") (pintype "bidirectional"))
      (node (ref "R2") (pin "1") (pinfunction "1_1") (pintype "passive"))
    )
    (net (code "102") (name "Net-(IC3-Y)") (class "Default")
      (node (ref "IC3") (pin "4") (pinfunction "Y_4") (pintype "output"))
      (node (ref "R5") (pin "2") (pinfunction "2_2") (pintype "passive"))
    )
    (net (code "103") (name "Net-(IC5-FB)") (class "Default")
      (node (ref "C13") (pin "2") (pinfunction "2_2") (pintype "passive"))
      (node (ref "IC5") (pin "1") (pinfunction "FB_1") (pintype "bidirectional"))
      (node (ref "R12") (pin "2") (pinfunction "2_2") (pintype "passive"))
      (node (ref "R13") (pin "1") (pinfunction "1_1") (pintype "passive"))
      (node (ref "TP-M2FB") (pin "TP") (pinfunction "P$1_TP") (pintype "bidirectional"))
    )
    (net (code "104") (name "Net-(IC5-LX)") (class "Default")
      (node (ref "IC5") (pin "6") (pinfunction "LX_6") (pintype "power_in"))
      (node (ref "L1") (pin "1") (pinfunction "1_1") (pintype "passive"))
      (node (ref "TP-LX") (pin "TP") (pinfunction "P$1_TP") (pintype "bidirectional"))
    )
    (net (code "105") (name "Net-(J4-Pad17)") (class "Default")
      (node (ref "J4") (pin "17") (pinfunction "17_17") (pintype "passive"))
      (node (ref "R61") (pin "1") (pinfunction "1_1") (pintype "passive"))
    )
    (net (code "106") (name "Net-(LED1-PadC)") (class "Default")
      (node (ref "LED1") (pin "C") (pinfunction "C_C") (pintype "passive"))
      (node (ref "R5") (pin "1") (pinfunction "1_1") (pintype "passive"))
    )
    (net (code "107") (name "Net-(LED2-PadC)") (class "Default")
      (node (ref "LED2") (pin "C") (pinfunction "C_C") (pintype "passive"))
      (node (ref "R10") (pin "1") (pinfunction "1_1") (pintype "passive"))
    )
    (net (code "108") (name "Net-(PCIE-DA5{slash}~{DSS}{slash}~{LED1})") (class "Default")
      (node (ref "PCIE") (pin "10") (pinfunction "DA5/~{DSS}/~{LED1}_10") (pintype "bidirectional"))
      (node (ref "R10") (pin "2") (pinfunction "2_2") (pintype "passive"))
    )
    (net (code "109") (name "Net-(PCIE-SUSCLK)") (class "Default")
      (node (ref "PCIE") (pin "68") (pinfunction "SUSCLK_68") (pintype "bidirectional"))
      (node (ref "TP-M2CLK") (pin "TP") (pinfunction "P$1_TP") (pintype "bidirectional"))
      (node (ref "X2") (pin "1") (pinfunction "CON_1") (pintype "input"))
    )
    (net (code "110") (name "PCIE_CLK_N") (class "Default")
      (node (ref "PCIE") (pin "53") (pinfunction "REFCLK_N_53") (pintype "bidirectional"))
      (node (ref "PI1") (pin "111") (pinfunction "11_111") (pintype "passive"))
    )
    (net (code "111") (name "PCIE_CLK_P") (class "Default")
      (node (ref "PCIE") (pin "55") (pinfunction "REFCLK_P_55") (pintype "bidirectional"))
      (node (ref "PI1") (pin "109") (pinfunction "9_109") (pintype "passive"))
    )
    (net (code "112") (name "PCIE_NCLKREQ") (class "Default")
      (node (ref "PCIE") (pin "52") (pinfunction "~{CLKREQ}_52") (pintype "bidirectional"))
      (node (ref "PI1") (pin "101") (pinfunction "1_101") (pintype "passive"))
    )
    (net (code "113") (name "PCIE_NRST") (class "Default")
      (node (ref "PCIE") (pin "50") (pinfunction "~{PERST}_50") (pintype "bidirectional"))
      (node (ref "PI1") (pin "110") (pinfunction "10_110") (pintype "passive"))
    )
    (net (code "114") (name "PCIE_NWAKE") (class "Default")
      (node (ref "PCIE") (pin "54") (pinfunction "~{PEWAKE}_54") (pintype "bidirectional"))
      (node (ref "PI1") (pin "103") (pinfunction "3_103") (pintype "passive"))
    )
    (net (code "115") (name "PCIE_PWR_EN") (class "Default")
      (node (ref "IC5") (pin "7") (pinfunction "EN_7") (pintype "bidirectional"))
      (node (ref "PI1") (pin "105") (pinfunction "5_105") (pintype "passive"))
      (node (ref "R11") (pin "1") (pinfunction "1_1") (pintype "passive"))
    )
    (net (code "116") (name "PCIE_RX_N") (class "Default")
      (node (ref "PCIE") (pin "43") (pinfunction "PET_P0_43") (pintype "bidirectional"))
      (node (ref "PI1") (pin "117") (pinfunction "17_117") (pintype "passive"))
    )
    (net (code "117") (name "PCIE_RX_P") (class "Default")
      (node (ref "PCIE") (pin "41") (pinfunction "PET_N0_41") (pintype "bidirectional"))
      (node (ref "PI1") (pin "115") (pinfunction "15_115") (pintype "passive"))
    )
    (net (code "118") (name "PCIE_TX_N") (class "Default")
      (node (ref "PCIE") (pin "49") (pinfunction "PER_P0_49") (pintype "bidirectional"))
      (node (ref "PI1") (pin "123") (pinfunction "23_123") (pintype "passive"))
    )
    (net (code "119") (name "PCIE_TX_P") (class "Default")
      (node (ref "PCIE") (pin "47") (pinfunction "PER_N0_47") (pintype "bidirectional"))
      (node (ref "PI1") (pin "121") (pinfunction "21_121") (pintype "passive"))
    )
    (net (code "120") (name "PMIC_ENABLE") (class "Default")
      (node (ref "JP2") (pin "12") (pinfunction "12_12") (pintype "bidirectional"))
      (node (ref "PI1") (pin "100") (pinfunction "100_100") (pintype "passive"))
    )
    (net (code "121") (name "PWM") (class "Default")
      (node (ref "FAN") (pin "3") (pinfunction "P$3_3") (pintype "bidirectional"))
      (node (ref "PI1") (pin "20") (pinfunction "20_20") (pintype "passive"))
    )
    (net (code "122") (name "PWR_BUT") (class "Default")
      (node (ref "JP2") (pin "14") (pinfunction "14_14") (pintype "bidirectional"))
      (node (ref "PI1") (pin "91") (pinfunction "91_91") (pintype "passive"))
      (node (ref "SW1") (pin "2") (pinfunction "2_2") (pintype "passive"))
      (node (ref "TP-BTN") (pin "TP") (pinfunction "P$1_TP") (pintype "bidirectional"))
    )
    (net (code "123") (name "RP2040_RST0") (class "Default")
      (node (ref "CON3") (pin "23") (pinfunction "23_23") (pintype "bidirectional"))
      (node (ref "MODULE_AIO") (pin "B18") (pinfunction "18_B18") (pintype "passive"))
    )
    (net (code "124") (name "RP2040_RST1") (class "Default")
      (node (ref "CON3") (pin "21") (pinfunction "21_21") (pintype "bidirectional"))
      (node (ref "MODULE_DIO") (pin "B18") (pinfunction "18_B18") (pintype "passive"))
    )
    (net (code "125") (name "SCL0") (class "Default")
      (node (ref "J3") (pin "20") (pinfunction "20_20") (pintype "passive"))
      (node (ref "PI1") (pin "79") (pinfunction "79_79") (pintype "passive"))
    )
    (net (code "126") (name "SCL1") (class "Default")
      (node (ref "ID") (pin "2") (pinfunction "2_2") (pintype "bidirectional"))
      (node (ref "J4") (pin "20") (pinfunction "20_20") (pintype "passive"))
      (node (ref "R4") (pin "2") (pinfunction "2_2") (pintype "passive"))
    )
    (net (code "127") (name "SDA0") (class "Default")
      (node (ref "J3") (pin "21") (pinfunction "21_21") (pintype "passive"))
      (node (ref "PI1") (pin "81") (pinfunction "81_81") (pintype "passive"))
    )
    (net (code "128") (name "SDA1") (class "Default")
      (node (ref "ID") (pin "4") (pinfunction "4_4") (pintype "bidirectional"))
      (node (ref "J4") (pin "21") (pinfunction "21_21") (pintype "passive"))
      (node (ref "R3") (pin "2") (pinfunction "2_2") (pintype "passive"))
    )
    (net (code "129") (name "SDO_A_0") (class "Default")
      (node (ref "CON2") (pin "15") (pinfunction "15_15") (pintype "bidirectional"))
      (node (ref "MODULE_AIO") (pin "A17") (pinfunction "17_A17") (pintype "passive"))
    )
    (net (code "130") (name "SDO_A_1") (class "Default")
      (node (ref "CON2") (pin "13") (pinfunction "13_13") (pintype "bidirectional"))
      (node (ref "MODULE_AIO") (pin "A18") (pinfunction "18_A18") (pintype "passive"))
    )
    (net (code "131") (name "SDO_A_2") (class "Default")
      (node (ref "CON2") (pin "11") (pinfunction "11_11") (pintype "bidirectional"))
      (node (ref "MODULE_AIO") (pin "A19") (pinfunction "19_A19") (pintype "passive"))
    )
    (net (code "132") (name "SDO_A_3") (class "Default")
      (node (ref "CON2") (pin "9") (pinfunction "9_9") (pintype "bidirectional"))
      (node (ref "MODULE_AIO") (pin "A20") (pinfunction "20_A20") (pintype "passive"))
    )
    (net (code "133") (name "SDO_B_0") (class "Default")
      (node (ref "CON2") (pin "7") (pinfunction "7_7") (pintype "bidirectional"))
      (node (ref "MODULE_AIO") (pin "A21") (pinfunction "21_A21") (pintype "passive"))
    )
    (net (code "134") (name "SDO_B_1") (class "Default")
      (node (ref "CON2") (pin "5") (pinfunction "5_5") (pintype "bidirectional"))
      (node (ref "MODULE_AIO") (pin "A22") (pinfunction "22_A22") (pintype "passive"))
    )
    (net (code "135") (name "SDO_B_2") (class "Default")
      (node (ref "CON2") (pin "3") (pinfunction "3_3") (pintype "bidirectional"))
      (node (ref "MODULE_AIO") (pin "A23") (pinfunction "23_A23") (pintype "passive"))
    )
    (net (code "136") (name "SDO_B_3") (class "Default")
      (node (ref "CON2") (pin "1") (pinfunction "1_1") (pintype "bidirectional"))
      (node (ref "MODULE_AIO") (pin "A24") (pinfunction "24_A24") (pintype "passive"))
    )
    (net (code "137") (name "SD_CLK") (class "Default")
      (node (ref "PI1") (pin "58") (pinfunction "58_58") (pintype "passive"))
      (node (ref "SD1") (pin "CLK") (pinfunction "CLK_CLK") (pintype "bidirectional"))
    )
    (net (code "138") (name "SD_CMD") (class "Default")
      (node (ref "PI1") (pin "61") (pinfunction "61_61") (pintype "passive"))
      (node (ref "SD1") (pin "CMD") (pinfunction "CMD_CMD") (pintype "bidirectional"))
    )
    (net (code "139") (name "SD_DAT0") (class "Default")
      (node (ref "PI1") (pin "64") (pinfunction "64_64") (pintype "passive"))
      (node (ref "SD1") (pin "DAT0") (pinfunction "DAT0_DAT0") (pintype "bidirectional"))
    )
    (net (code "140") (name "SD_DAT1") (class "Default")
      (node (ref "PI1") (pin "68") (pinfunction "68_68") (pintype "passive"))
      (node (ref "SD1") (pin "DAT1") (pinfunction "DAT1_DAT1") (pintype "bidirectional"))
    )
    (net (code "141") (name "SD_DAT2") (class "Default")
      (node (ref "PI1") (pin "70") (pinfunction "70_70") (pintype "passive"))
      (node (ref "SD1") (pin "DAT2") (pinfunction "DAT2_DAT2") (pintype "bidirectional"))
    )
    (net (code "142") (name "SD_DAT3") (class "Default")
      (node (ref "PI1") (pin "62") (pinfunction "62_62") (pintype "passive"))
      (node (ref "SD1") (pin "DAT3/CD") (pinfunction "CD/DAT3_DAT3/CD") (pintype "bidirectional"))
    )
    (net (code "143") (name "SD_PWR") (class "Default")
      (node (ref "C10") (pin "1") (pinfunction "1_1") (pintype "passive"))
      (node (ref "IC1") (pin "1") (pinfunction "OUT_1") (pintype "power_in"))
      (node (ref "SD1") (pin "VDD") (pinfunction "VDD_VDD") (pintype "bidirectional"))
      (node (ref "TP-VSD") (pin "TP") (pinfunction "P$1_TP") (pintype "bidirectional"))
    )
    (net (code "144") (name "SD_PWR_ON") (class "Default")
      (node (ref "IC1") (pin "4") (pinfunction "EN_4") (pintype "bidirectional"))
      (node (ref "PI1") (pin "76") (pinfunction "76_76") (pintype "passive"))
    )
    (net (code "145") (name "SPI_ADC_CS") (class "Default")
      (node (ref "CON2") (pin "39") (pinfunction "39_39") (pintype "bidirectional"))
      (node (ref "MODULE_AIO") (pin "A2") (pinfunction "2_A2") (pintype "passive"))
    )
    (net (code "146") (name "SPI_AIOMODULE_CS0") (class "Default")
      (node (ref "CON3") (pin "5") (pinfunction "5_5") (pintype "bidirectional"))
      (node (ref "MODULE_AIO") (pin "A29") (pinfunction "29_A29") (pintype "passive"))
      (node (ref "MODULE_AIO") (pin "B29") (pinfunction "29_B29") (pintype "passive"))
    )
    (net (code "147") (name "SPI_AIOMODULE_MISO") (class "Default")
      (node (ref "CON3") (pin "11") (pinfunction "11_11") (pintype "bidirectional"))
      (node (ref "MODULE_AIO") (pin "A26") (pinfunction "26_A26") (pintype "passive"))
      (node (ref "MODULE_AIO") (pin "B26") (pinfunction "26_B26") (pintype "passive"))
    )
    (net (code "148") (name "SPI_AIOMODULE_MOSI") (class "Default")
      (node (ref "CON3") (pin "9") (pinfunction "9_9") (pintype "bidirectional"))
      (node (ref "MODULE_AIO") (pin "A27") (pinfunction "27_A27") (pintype "passive"))
      (node (ref "MODULE_AIO") (pin "B27") (pinfunction "27_B27") (pintype "passive"))
    )
    (net (code "149") (name "SPI_AIOMODULE_SCK") (class "Default")
      (node (ref "CON3") (pin "7") (pinfunction "7_7") (pintype "bidirectional"))
      (node (ref "MODULE_AIO") (pin "A28") (pinfunction "28_A28") (pintype "passive"))
      (node (ref "MODULE_AIO") (pin "B28") (pinfunction "28_B28") (pintype "passive"))
    )
    (net (code "150") (name "SPI_DAC_CS") (class "Default")
      (node (ref "CON2") (pin "21") (pinfunction "21_21") (pintype "bidirectional"))
      (node (ref "MODULE_AIO") (pin "B2") (pinfunction "2_B2") (pintype "passive"))
    )
    (net (code "151") (name "SPI_DIOMODULE_CS1") (class "Default")
      (node (ref "CON3") (pin "3") (pinfunction "3_3") (pintype "bidirectional"))
      (node (ref "MODULE_DIO") (pin "A29") (pinfunction "29_A29") (pintype "passive"))
      (node (ref "MODULE_DIO") (pin "B29") (pinfunction "29_B29") (pintype "passive"))
    )
    (net (code "152") (name "SPI_DIOMODULE_MISO") (class "Default")
      (node (ref "MODULE_DIO") (pin "A26") (pinfunction "26_A26") (pintype "passive"))
      (node (ref "MODULE_DIO") (pin "B26") (pinfunction "26_B26") (pintype "passive"))
    )
    (net (code "153") (name "SPI_DIOMODULE_MOSI") (class "Default")
      (node (ref "MODULE_DIO") (pin "A27") (pinfunction "27_A27") (pintype "passive"))
      (node (ref "MODULE_DIO") (pin "B27") (pinfunction "27_B27") (pintype "passive"))
    )
    (net (code "154") (name "SPI_DIOMODULE_SCK") (class "Default")
      (node (ref "MODULE_DIO") (pin "A28") (pinfunction "28_A28") (pintype "passive"))
      (node (ref "MODULE_DIO") (pin "B28") (pinfunction "28_B28") (pintype "passive"))
    )
    (net (code "155") (name "SPI_DIO_CS0") (class "Default")
      (node (ref "CON3") (pin "33") (pinfunction "33_33") (pintype "bidirectional"))
      (node (ref "MODULE_DIO") (pin "A2") (pinfunction "2_A2") (pintype "passive"))
    )
    (net (code "156") (name "SPI_DIO_CS1") (class "Default")
      (node (ref "CON3") (pin "31") (pinfunction "31_31") (pintype "bidirectional"))
      (node (ref "MODULE_DIO") (pin "A3") (pinfunction "3_A3") (pintype "passive"))
    )
    (net (code "157") (name "SPI_MISO") (class "Default")
      (node (ref "CON2") (pin "29") (pinfunction "29_29") (pintype "bidirectional"))
      (node (ref "MODULE_AIO") (pin "A7") (pinfunction "7_A7") (pintype "passive"))
      (node (ref "MODULE_AIO") (pin "B7") (pinfunction "7_B7") (pintype "passive"))
      (node (ref "MODULE_DIO") (pin "A7") (pinfunction "7_A7") (pintype "passive"))
      (node (ref "MODULE_DIO") (pin "B7") (pinfunction "7_B7") (pintype "passive"))
    )
    (net (code "158") (name "SPI_MOSI") (class "Default")
      (node (ref "CON2") (pin "31") (pinfunction "31_31") (pintype "bidirectional"))
      (node (ref "MODULE_AIO") (pin "A6") (pinfunction "6_A6") (pintype "passive"))
      (node (ref "MODULE_AIO") (pin "B6") (pinfunction "6_B6") (pintype "passive"))
      (node (ref "MODULE_DIO") (pin "A6") (pinfunction "6_A6") (pintype "passive"))
      (node (ref "MODULE_DIO") (pin "B6") (pinfunction "6_B6") (pintype "passive"))
    )
    (net (code "159") (name "SPI_PGA_CS0") (class "Default")
      (node (ref "CON2") (pin "37") (pinfunction "37_37") (pintype "bidirectional"))
      (node (ref "MODULE_AIO") (pin "A3") (pinfunction "3_A3") (pintype "passive"))
    )
    (net (code "160") (name "SPI_PGA_CS1") (class "Default")
      (node (ref "CON2") (pin "35") (pinfunction "35_35") (pintype "bidirectional"))
      (node (ref "MODULE_AIO") (pin "A4") (pinfunction "4_A4") (pintype "passive"))
    )
    (net (code "161") (name "SPI_SCK") (class "Default")
      (node (ref "CON2") (pin "33") (pinfunction "33_33") (pintype "bidirectional"))
      (node (ref "MODULE_AIO") (pin "A5") (pinfunction "5_A5") (pintype "passive"))
      (node (ref "MODULE_AIO") (pin "B5") (pinfunction "5_B5") (pintype "passive"))
      (node (ref "MODULE_DIO") (pin "A5") (pinfunction "5_A5") (pintype "passive"))
      (node (ref "MODULE_DIO") (pin "B5") (pinfunction "5_B5") (pintype "passive"))
    )
    (net (code "162") (name "SWCLK") (class "Default")
      (node (ref "CON3") (pin "15") (pinfunction "15_15") (pintype "bidirectional"))
      (node (ref "MODULE_AIO") (pin "B23") (pinfunction "23_B23") (pintype "passive"))
      (node (ref "MODULE_DIO") (pin "B23") (pinfunction "23_B23") (pintype "passive"))
    )
    (net (code "163") (name "SWDIO") (class "Default")
      (node (ref "CON3") (pin "13") (pinfunction "13_13") (pintype "bidirectional"))
      (node (ref "MODULE_AIO") (pin "B24") (pinfunction "24_B24") (pintype "passive"))
      (node (ref "MODULE_DIO") (pin "B24") (pinfunction "24_B24") (pintype "passive"))
    )
    (net (code "164") (name "SYNC_OUT") (class "Default")
      (node (ref "JP2") (pin "6") (pinfunction "6_6") (pintype "bidirectional"))
      (node (ref "PI1") (pin "17") (pinfunction "17_17") (pintype "passive"))
    )
    (net (code "165") (name "TACHO") (class "Default")
      (node (ref "FAN") (pin "1") (pinfunction "P$1_1") (pintype "bidirectional"))
      (node (ref "PI1") (pin "15") (pinfunction "15_15") (pintype "passive"))
    )
    (net (code "166") (name "TR0_TAP") (class "Default")
      (node (ref "ETH1") (pin "VC1") (pinfunction "VC1_VC1") (pintype "bidirectional"))
      (node (ref "POE") (pin "3") (pinfunction "3_3") (pintype "bidirectional"))
    )
    (net (code "167") (name "TR1_TAP") (class "Default")
      (node (ref "ETH1") (pin "VC2") (pinfunction "VC2_VC2") (pintype "bidirectional"))
      (node (ref "POE") (pin "1") (pinfunction "1_1") (pintype "bidirectional"))
    )
    (net (code "168") (name "TR2_TAP") (class "Default")
      (node (ref "ETH1") (pin "VC3") (pinfunction "VC3_VC3") (pintype "bidirectional"))
      (node (ref "POE") (pin "2") (pinfunction "2_2") (pintype "bidirectional"))
    )
    (net (code "169") (name "TR3_TAP") (class "Default")
      (node (ref "ETH1") (pin "VC4") (pinfunction "VC4_VC4") (pintype "bidirectional"))
      (node (ref "POE") (pin "4") (pinfunction "4_4") (pintype "bidirectional"))
    )
    (net (code "170") (name "TRD0_N") (class "Default")
      (node (ref "D2") (pin "2") (pinfunction "D1-_2") (pintype "bidirectional"))
      (node (ref "D2") (pin "9") (pinfunction "D1-_9") (pintype "bidirectional"))
      (node (ref "ETH1") (pin "TD1-") (pinfunction "TD1-_TD1-") (pintype "bidirectional"))
      (node (ref "PI1") (pin "9") (pinfunction "9_9") (pintype "passive"))
    )
    (net (code "171") (name "TRD0_P") (class "Default")
      (node (ref "D2") (pin "1") (pinfunction "D1+_1") (pintype "bidirectional"))
      (node (ref "D2") (pin "10") (pinfunction "D1+_10") (pintype "bidirectional"))
      (node (ref "ETH1") (pin "TD1+") (pinfunction "TD1+_TD1+") (pintype "bidirectional"))
      (node (ref "PI1") (pin "11") (pinfunction "11_11") (pintype "passive"))
    )
    (net (code "172") (name "TRD1_N") (class "Default")
      (node (ref "D2") (pin "4") (pinfunction "D2+_4") (pintype "bidirectional"))
      (node (ref "D2") (pin "7") (pinfunction "D2+_7") (pintype "bidirectional"))
      (node (ref "ETH1") (pin "TD2-") (pinfunction "TD2-_TD2-") (pintype "bidirectional"))
      (node (ref "PI1") (pin "5") (pinfunction "5_5") (pintype "passive"))
    )
    (net (code "173") (name "TRD1_P") (class "Default")
      (node (ref "D2") (pin "5") (pinfunction "D2-_5") (pintype "bidirectional"))
      (node (ref "D2") (pin "6") (pinfunction "D2-_6") (pintype "bidirectional"))
      (node (ref "ETH1") (pin "TD2+") (pinfunction "TD2+_TD2+") (pintype "bidirectional"))
      (node (ref "PI1") (pin "3") (pinfunction "3_3") (pintype "passive"))
    )
    (net (code "174") (name "TRD2_N") (class "Default")
      (node (ref "D1") (pin "4") (pinfunction "D2+_4") (pintype "bidirectional"))
      (node (ref "D1") (pin "7") (pinfunction "D2+_7") (pintype "bidirectional"))
      (node (ref "ETH1") (pin "TD3-") (pinfunction "TD3-_TD3-") (pintype "bidirectional"))
      (node (ref "PI1") (pin "10") (pinfunction "10_10") (pintype "passive"))
    )
    (net (code "175") (name "TRD2_P") (class "Default")
      (node (ref "D1") (pin "5") (pinfunction "D2-_5") (pintype "bidirectional"))
      (node (ref "D1") (pin "6") (pinfunction "D2-_6") (pintype "bidirectional"))
      (node (ref "ETH1") (pin "TD3+") (pinfunction "TD3+_TD3+") (pintype "bidirectional"))
      (node (ref "PI1") (pin "12") (pinfunction "12_12") (pintype "passive"))
    )
    (net (code "176") (name "TRD3_N") (class "Default")
      (node (ref "D1") (pin "2") (pinfunction "D1-_2") (pintype "bidirectional"))
      (node (ref "D1") (pin "9") (pinfunction "D1-_9") (pintype "bidirectional"))
      (node (ref "ETH1") (pin "TD4-") (pinfunction "TD4-_TD4-") (pintype "bidirectional"))
      (node (ref "PI1") (pin "6") (pinfunction "6_6") (pintype "passive"))
    )
    (net (code "177") (name "TRD3_P") (class "Default")
      (node (ref "D1") (pin "1") (pinfunction "D1+_1") (pintype "bidirectional"))
      (node (ref "D1") (pin "10") (pinfunction "D1+_10") (pintype "bidirectional"))
      (node (ref "ETH1") (pin "TD4+") (pinfunction "TD4+_TD4+") (pintype "bidirectional"))
      (node (ref "PI1") (pin "4") (pinfunction "4_4") (pintype "passive"))
    )
    (net (code "178") (name "UART0_RX") (class "Default")
      (node (ref "CON3") (pin "19") (pinfunction "19_19") (pintype "bidirectional"))
      (node (ref "MODULE_AIO") (pin "B20") (pinfunction "20_B20") (pintype "passive"))
      (node (ref "MODULE_DIO") (pin "B20") (pinfunction "20_B20") (pintype "passive"))
    )
    (net (code "179") (name "UART0_TX") (class "Default")
      (node (ref "CON3") (pin "17") (pinfunction "17_17") (pintype "bidirectional"))
      (node (ref "MODULE_AIO") (pin "B21") (pinfunction "21_B21") (pintype "passive"))
      (node (ref "MODULE_DIO") (pin "B21") (pinfunction "21_B21") (pintype "passive"))
    )
    (net (code "180") (name "USB2_N") (class "Default")
      (node (ref "PI1") (pin "104") (pinfunction "4_104") (pintype "passive"))
      (node (ref "USBC") (pin "A7") (pinfunction "D-1_A7") (pintype "passive"))
      (node (ref "USBC") (pin "B7") (pinfunction "D-2_B7") (pintype "passive"))
    )
    (net (code "181") (name "USB2_P") (class "Default")
      (node (ref "PI1") (pin "106") (pinfunction "6_106") (pintype "passive"))
      (node (ref "USBC") (pin "A6") (pinfunction "D+1_A6") (pintype "passive"))
      (node (ref "USBC") (pin "B6") (pinfunction "D+2_B6") (pintype "passive"))
    )
    (net (code "182") (name "USB3-0-D_N") (class "Default")
      (node (ref "J1") (pin "2") (pinfunction "D-_2") (pintype "passive"))
      (node (ref "PI1") (pin "135") (pinfunction "35_135") (pintype "passive"))
    )
    (net (code "183") (name "USB3-0-D_P") (class "Default")
      (node (ref "J1") (pin "3") (pinfunction "D+_3") (pintype "passive"))
      (node (ref "PI1") (pin "133") (pinfunction "33_133") (pintype "passive"))
    )
    (net (code "184") (name "USB3-0-RX_N") (class "Default")
      (node (ref "J1") (pin "5") (pinfunction "STDA_SSRX-_5") (pintype "passive"))
      (node (ref "PI1") (pin "127") (pinfunction "27_127") (pintype "passive"))
    )
    (net (code "185") (name "USB3-0-RX_P") (class "Default")
      (node (ref "J1") (pin "6") (pinfunction "STDA_SSRX+_6") (pintype "passive"))
      (node (ref "PI1") (pin "129") (pinfunction "29_129") (pintype "passive"))
    )
    (net (code "186") (name "USB3-0-TX_N") (class "Default")
      (node (ref "J1") (pin "8") (pinfunction "STDA_SSTX-_8") (pintype "passive"))
      (node (ref "PI1") (pin "139") (pinfunction "39_139") (pintype "passive"))
    )
    (net (code "187") (name "USB3-0-TX_P") (class "Default")
      (node (ref "J1") (pin "9") (pinfunction "STDA_SSTX+_9") (pintype "passive"))
      (node (ref "PI1") (pin "141") (pinfunction "41_141") (pintype "passive"))
    )
    (net (code "188") (name "USB3-1-D_N") (class "Default")
      (node (ref "J2") (pin "2") (pinfunction "D-_2") (pintype "passive"))
      (node (ref "PI1") (pin "166") (pinfunction "66_166") (pintype "passive"))
    )
    (net (code "189") (name "USB3-1-D_P") (class "Default")
      (node (ref "J2") (pin "3") (pinfunction "D+_3") (pintype "passive"))
      (node (ref "PI1") (pin "164") (pinfunction "64_164") (pintype "passive"))
    )
    (net (code "190") (name "USB3-1-RX_N") (class "Default")
      (node (ref "J2") (pin "5") (pinfunction "STDA_SSRX-_5") (pintype "passive"))
      (node (ref "PI1") (pin "158") (pinfunction "58_158") (pintype "passive"))
    )
    (net (code "191") (name "USB3-1-RX_P") (class "Default")
      (node (ref "J2") (pin "6") (pinfunction "STDA_SSRX+_6") (pintype "passive"))
      (node (ref "PI1") (pin "160") (pinfunction "60_160") (pintype "passive"))
    )
    (net (code "192") (name "USB3-1-TX_N") (class "Default")
      (node (ref "J2") (pin "8") (pinfunction "STDA_SSTX-_8") (pintype "passive"))
      (node (ref "PI1") (pin "170") (pinfunction "70_170") (pintype "passive"))
    )
    (net (code "193") (name "USB3-1-TX_P") (class "Default")
      (node (ref "J2") (pin "9") (pinfunction "STDA_SSTX+_9") (pintype "passive"))
      (node (ref "PI1") (pin "172") (pinfunction "72_172") (pintype "passive"))
    )
    (net (code "194") (name "USBOTG_ID") (class "Default")
      (node (ref "JP2") (pin "10") (pinfunction "10_10") (pintype "bidirectional"))
      (node (ref "PI1") (pin "102") (pinfunction "2_102") (pintype "passive"))
    )
    (net (code "195") (name "VBAT") (class "Default")
      (node (ref "PI1") (pin "75") (pinfunction "75_75") (pintype "passive"))
    )
    (net (code "196") (name "VBUS") (class "Default")
      (node (ref "C6") (pin "1") (pinfunction "1_1") (pintype "passive"))
      (node (ref "C7") (pin "1") (pinfunction "1_1") (pintype "passive"))
      (node (ref "C8") (pin "1") (pinfunction "1_1") (pintype "passive"))
      (node (ref "IC2") (pin "6") (pinfunction "OUT_6") (pintype "bidirectional"))
      (node (ref "J1") (pin "1") (pinfunction "VBUS_1") (pintype "passive"))
      (node (ref "J2") (pin "1") (pinfunction "VBUS_1") (pintype "passive"))
      (node (ref "TP-VBUS") (pin "TP") (pinfunction "P$1_TP") (pintype "bidirectional"))
    )
    (net (code "197") (name "VBUS_EN") (class "Default")
      (node (ref "IC2") (pin "3") (pinfunction "EN_3") (pintype "bidirectional"))
      (node (ref "PI1") (pin "112") (pinfunction "12_112") (pintype "passive"))
    )
    (net (code "198") (name "WL_NDIS") (class "Default")
      (node (ref "JP3") (pin "1") (pinfunction "1_1") (pintype "bidirectional"))
      (node (ref "PI1") (pin "90") (pinfunction "90_90") (pintype "passive"))
    )
    (net (code "199") (name "unconnected-(CON2-Pad2)") (class "Default")
      (node (ref "CON2") (pin "2") (pinfunction "2_2") (pintype "bidirectional"))
    )
    (net (code "200") (name "unconnected-(CON2-Pad4)") (class "Default")
      (node (ref "CON2") (pin "4") (pinfunction "4_4") (pintype "bidirectional"))
    )
    (net (code "201") (name "unconnected-(CON2-Pad6)") (class "Default")
      (node (ref "CON2") (pin "6") (pinfunction "6_6") (pintype "bidirectional"))
    )
    (net (code "202") (name "unconnected-(CON2-Pad8)") (class "Default")
      (node (ref "CON2") (pin "8") (pinfunction "8_8") (pintype "bidirectional"))
    )
    (net (code "203") (name "unconnected-(CON2-Pad10)") (class "Default")
      (node (ref "CON2") (pin "10") (pinfunction "10_10") (pintype "bidirectional"))
    )
    (net (code "204") (name "unconnected-(CON2-Pad12)") (class "Default")
      (node (ref "CON2") (pin "12") (pinfunction "12_12") (pintype "bidirectional"))
    )
    (net (code "205") (name "unconnected-(CON2-Pad14)") (class "Default")
      (node (ref "CON2") (pin "14") (pinfunction "14_14") (pintype "bidirectional"))
    )
    (net (code "206") (name "unconnected-(CON2-Pad16)") (class "Default")
      (node (ref "CON2") (pin "16") (pinfunction "16_16") (pintype "bidirectional"))
    )
    (net (code "207") (name "unconnected-(CON3-Pad26)") (class "Default")
      (node (ref "CON3") (pin "26") (pinfunction "26_26") (pintype "bidirectional"))
    )
    (net (code "208") (name "unconnected-(CON3-Pad28)") (class "Default")
      (node (ref "CON3") (pin "28") (pinfunction "28_28") (pintype "bidirectional"))
    )
    (net (code "209") (name "unconnected-(CON3-Pad35)") (class "Default")
      (node (ref "CON3") (pin "35") (pinfunction "35_35") (pintype "bidirectional"))
    )
    (net (code "210") (name "unconnected-(CON3-Pad36)") (class "Default")
      (node (ref "CON3") (pin "36") (pinfunction "36_36") (pintype "bidirectional"))
    )
    (net (code "211") (name "unconnected-(CON3-Pad37)") (class "Default")
      (node (ref "CON3") (pin "37") (pinfunction "37_37") (pintype "bidirectional"))
    )
    (net (code "212") (name "unconnected-(CON3-Pad38)") (class "Default")
      (node (ref "CON3") (pin "38") (pinfunction "38_38") (pintype "bidirectional"))
    )
    (net (code "213") (name "unconnected-(CON3-Pad39)") (class "Default")
      (node (ref "CON3") (pin "39") (pinfunction "39_39") (pintype "bidirectional"))
    )
    (net (code "214") (name "unconnected-(CON3-Pad40)") (class "Default")
      (node (ref "CON3") (pin "40") (pinfunction "40_40") (pintype "bidirectional"))
    )
    (net (code "215") (name "unconnected-(HDMI1-CEC-Pad14)") (class "Default")
      (node (ref "HDMI1") (pin "14") (pinfunction "CEC_14") (pintype "passive"))
    )
    (net (code "216") (name "unconnected-(HDMI2-CEC-Pad14)") (class "Default")
      (node (ref "HDMI2") (pin "14") (pinfunction "CEC_14") (pintype "passive"))
    )
    (net (code "217") (name "unconnected-(IC1-NFLG-Pad3)") (class "Default")
      (node (ref "IC1") (pin "3") (pinfunction "NFLG_3") (pintype "bidirectional"))
    )
    (net (code "218") (name "unconnected-(IC2-~{FAULT}-Pad4)") (class "Default")
      (node (ref "IC2") (pin "4") (pinfunction "~{FAULT}_4") (pintype "bidirectional"))
    )
    (net (code "219") (name "unconnected-(IC5-NC-Pad5)") (class "Default")
      (node (ref "IC5") (pin "5") (pinfunction "NC_5") (pintype "no_connect"))
    )
    (net (code "220") (name "unconnected-(IC5-PG-Pad2)") (class "Default")
      (node (ref "IC5") (pin "2") (pinfunction "PG_2") (pintype "bidirectional"))
    )
    (net (code "221") (name "unconnected-(J4-Pad18)") (class "Default")
      (node (ref "J4") (pin "18") (pinfunction "18_18") (pintype "passive"))
    )
    (net (code "222") (name "unconnected-(JP2-Pad8)") (class "Default")
      (node (ref "JP2") (pin "8") (pinfunction "8_8") (pintype "bidirectional"))
    )
    (net (code "223") (name "unconnected-(MODULE_AIOB-3-PadB3)") (class "Default")
      (node (ref "MODULE_AIO") (pin "B3") (pinfunction "3_B3") (pintype "passive"))
    )
    (net (code "224") (name "unconnected-(MODULE_AIOB-4-PadB4)") (class "Default")
      (node (ref "MODULE_AIO") (pin "B4") (pinfunction "4_B4") (pintype "passive"))
    )
    (net (code "225") (name "unconnected-(MODULE_AIOB-11-PadB11)") (class "Default")
      (node (ref "MODULE_AIO") (pin "B11") (pinfunction "11_B11") (pintype "passive"))
    )
    (net (code "226") (name "unconnected-(MODULE_AIOB-17-PadB17)") (class "Default")
      (node (ref "MODULE_AIO") (pin "B17") (pinfunction "17_B17") (pintype "passive"))
    )
    (net (code "227") (name "unconnected-(MODULE_DIOA-4-PadA4)") (class "Default")
      (node (ref "MODULE_DIO") (pin "A4") (pinfunction "4_A4") (pintype "passive"))
    )
    (net (code "228") (name "unconnected-(MODULE_DIOA-17-PadA17)") (class "Default")
      (node (ref "MODULE_DIO") (pin "A17") (pinfunction "17_A17") (pintype "passive"))
    )
    (net (code "229") (name "unconnected-(MODULE_DIOA-18-PadA18)") (class "Default")
      (node (ref "MODULE_DIO") (pin "A18") (pinfunction "18_A18") (pintype "passive"))
    )
    (net (code "230") (name "unconnected-(MODULE_DIOA-19-PadA19)") (class "Default")
      (node (ref "MODULE_DIO") (pin "A19") (pinfunction "19_A19") (pintype "passive"))
    )
    (net (code "231") (name "unconnected-(MODULE_DIOA-20-PadA20)") (class "Default")
      (node (ref "MODULE_DIO") (pin "A20") (pinfunction "20_A20") (pintype "passive"))
    )
    (net (code "232") (name "unconnected-(MODULE_DIOA-21-PadA21)") (class "Default")
      (node (ref "MODULE_DIO") (pin "A21") (pinfunction "21_A21") (pintype "passive"))
    )
    (net (code "233") (name "unconnected-(MODULE_DIOA-22-PadA22)") (class "Default")
      (node (ref "MODULE_DIO") (pin "A22") (pinfunction "22_A22") (pintype "passive"))
    )
    (net (code "234") (name "unconnected-(MODULE_DIOA-23-PadA23)") (class "Default")
      (node (ref "MODULE_DIO") (pin "A23") (pinfunction "23_A23") (pintype "passive"))
    )
    (net (code "235") (name "unconnected-(MODULE_DIOA-24-PadA24)") (class "Default")
      (node (ref "MODULE_DIO") (pin "A24") (pinfunction "24_A24") (pintype "passive"))
    )
    (net (code "236") (name "unconnected-(MODULE_DIOB-2-PadB2)") (class "Default")
      (node (ref "MODULE_DIO") (pin "B2") (pinfunction "2_B2") (pintype "passive"))
    )
    (net (code "237") (name "unconnected-(MODULE_DIOB-3-PadB3)") (class "Default")
      (node (ref "MODULE_DIO") (pin "B3") (pinfunction "3_B3") (pintype "passive"))
    )
    (net (code "238") (name "unconnected-(MODULE_DIOB-4-PadB4)") (class "Default")
      (node (ref "MODULE_DIO") (pin "B4") (pinfunction "4_B4") (pintype "passive"))
    )
    (net (code "239") (name "unconnected-(MODULE_DIOB-11-PadB11)") (class "Default")
      (node (ref "MODULE_DIO") (pin "B11") (pinfunction "11_B11") (pintype "passive"))
    )
    (net (code "240") (name "unconnected-(MODULE_DIOB-12-PadB12)") (class "Default")
      (node (ref "MODULE_DIO") (pin "B12") (pinfunction "12_B12") (pintype "passive"))
    )
    (net (code "241") (name "unconnected-(MODULE_DIOB-13-PadB13)") (class "Default")
      (node (ref "MODULE_DIO") (pin "B13") (pinfunction "13_B13") (pintype "passive"))
    )
    (net (code "242") (name "unconnected-(MODULE_DIOB-17-PadB17)") (class "Default")
      (node (ref "MODULE_DIO") (pin "B17") (pinfunction "17_B17") (pintype "passive"))
    )
    (net (code "243") (name "unconnected-(PCIE-DEVSLP-Pad38)") (class "Default")
      (node (ref "PCIE") (pin "38") (pinfunction "DEVSLP_38") (pintype "bidirectional"))
    )
    (net (code "244") (name "unconnected-(PCIE-NC1-Pad58)") (class "Default")
      (node (ref "PCIE") (pin "58") (pinfunction "NC1_58") (pintype "bidirectional"))
    )
    (net (code "245") (name "unconnected-(PCIE-NC2-Pad56)") (class "Default")
      (node (ref "PCIE") (pin "56") (pinfunction "NC2_56") (pintype "bidirectional"))
    )
    (net (code "246") (name "unconnected-(PCIE-NC3-Pad48)") (class "Default")
      (node (ref "PCIE") (pin "48") (pinfunction "NC3_48") (pintype "bidirectional"))
    )
    (net (code "247") (name "unconnected-(PCIE-NC4-Pad46)") (class "Default")
      (node (ref "PCIE") (pin "46") (pinfunction "NC4_46") (pintype "bidirectional"))
    )
    (net (code "248") (name "unconnected-(PCIE-NC5-Pad44)") (class "Default")
      (node (ref "PCIE") (pin "44") (pinfunction "NC5_44") (pintype "bidirectional"))
    )
    (net (code "249") (name "unconnected-(PCIE-NC6-Pad42)") (class "Default")
      (node (ref "PCIE") (pin "42") (pinfunction "NC6_42") (pintype "bidirectional"))
    )
    (net (code "250") (name "unconnected-(PCIE-NC7-Pad40)") (class "Default")
      (node (ref "PCIE") (pin "40") (pinfunction "NC7_40") (pintype "bidirectional"))
    )
    (net (code "251") (name "unconnected-(PCIE-NC8-Pad36)") (class "Default")
      (node (ref "PCIE") (pin "36") (pinfunction "NC8_36") (pintype "bidirectional"))
    )
    (net (code "252") (name "unconnected-(PCIE-NC9-Pad34)") (class "Default")
      (node (ref "PCIE") (pin "34") (pinfunction "NC9_34") (pintype "bidirectional"))
    )
    (net (code "253") (name "unconnected-(PCIE-NC10-Pad32)") (class "Default")
      (node (ref "PCIE") (pin "32") (pinfunction "NC10_32") (pintype "bidirectional"))
    )
    (net (code "254") (name "unconnected-(PCIE-NC11-Pad30)") (class "Default")
      (node (ref "PCIE") (pin "30") (pinfunction "NC11_30") (pintype "bidirectional"))
    )
    (net (code "255") (name "unconnected-(PCIE-NC12-Pad28)") (class "Default")
      (node (ref "PCIE") (pin "28") (pinfunction "NC12_28") (pintype "bidirectional"))
    )
    (net (code "256") (name "unconnected-(PCIE-NC13-Pad26)") (class "Default")
      (node (ref "PCIE") (pin "26") (pinfunction "NC13_26") (pintype "bidirectional"))
    )
    (net (code "257") (name "unconnected-(PCIE-NC14-Pad24)") (class "Default")
      (node (ref "PCIE") (pin "24") (pinfunction "NC14_24") (pintype "bidirectional"))
    )
    (net (code "258") (name "unconnected-(PCIE-NC15-Pad22)") (class "Default")
      (node (ref "PCIE") (pin "22") (pinfunction "NC15_22") (pintype "bidirectional"))
    )
    (net (code "259") (name "unconnected-(PCIE-NC16-Pad20)") (class "Default")
      (node (ref "PCIE") (pin "20") (pinfunction "NC16_20") (pintype "bidirectional"))
    )
    (net (code "260") (name "unconnected-(PCIE-NC17-Pad8)") (class "Default")
      (node (ref "PCIE") (pin "8") (pinfunction "NC17_8") (pintype "bidirectional"))
    )
    (net (code "261") (name "unconnected-(PCIE-NC18-Pad6)") (class "Default")
      (node (ref "PCIE") (pin "6") (pinfunction "NC18_6") (pintype "bidirectional"))
    )
    (net (code "262") (name "unconnected-(PCIE-NC19-Pad67)") (class "Default")
      (node (ref "PCIE") (pin "67") (pinfunction "NC19_67") (pintype "bidirectional"))
    )
    (net (code "263") (name "unconnected-(PCIE-PEDET-Pad69)") (class "Default")
      (node (ref "PCIE") (pin "69") (pinfunction "PEDET_69") (pintype "bidirectional"))
    )
    (net (code "264") (name "unconnected-(PCIE-PER_N1-Pad35)") (class "Default")
      (node (ref "PCIE") (pin "35") (pinfunction "PER_N1_35") (pintype "bidirectional"))
    )
    (net (code "265") (name "unconnected-(PCIE-PER_N2-Pad23)") (class "Default")
      (node (ref "PCIE") (pin "23") (pinfunction "PER_N2_23") (pintype "bidirectional"))
    )
    (net (code "266") (name "unconnected-(PCIE-PER_N3-Pad11)") (class "Default")
      (node (ref "PCIE") (pin "11") (pinfunction "PER_N3_11") (pintype "bidirectional"))
    )
    (net (code "267") (name "unconnected-(PCIE-PER_P1-Pad37)") (class "Default")
      (node (ref "PCIE") (pin "37") (pinfunction "PER_P1_37") (pintype "bidirectional"))
    )
    (net (code "268") (name "unconnected-(PCIE-PER_P2-Pad25)") (class "Default")
      (node (ref "PCIE") (pin "25") (pinfunction "PER_P2_25") (pintype "bidirectional"))
    )
    (net (code "269") (name "unconnected-(PCIE-PER_P3-Pad13)") (class "Default")
      (node (ref "PCIE") (pin "13") (pinfunction "PER_P3_13") (pintype "bidirectional"))
    )
    (net (code "270") (name "unconnected-(PCIE-PET_N1-Pad29)") (class "Default")
      (node (ref "PCIE") (pin "29") (pinfunction "PET_N1_29") (pintype "bidirectional"))
    )
    (net (code "271") (name "unconnected-(PCIE-PET_N2-Pad17)") (class "Default")
      (node (ref "PCIE") (pin "17") (pinfunction "PET_N2_17") (pintype "bidirectional"))
    )
    (net (code "272") (name "unconnected-(PCIE-PET_N3-Pad5)") (class "Default")
      (node (ref "PCIE") (pin "5") (pinfunction "PET_N3_5") (pintype "bidirectional"))
    )
    (net (code "273") (name "unconnected-(PCIE-PET_P1-Pad31)") (class "Default")
      (node (ref "PCIE") (pin "31") (pinfunction "PET_P1_31") (pintype "bidirectional"))
    )
    (net (code "274") (name "unconnected-(PCIE-PET_P2-Pad19)") (class "Default")
      (node (ref "PCIE") (pin "19") (pinfunction "PET_P2_19") (pintype "bidirectional"))
    )
    (net (code "275") (name "unconnected-(PCIE-PET_P3-Pad7)") (class "Default")
      (node (ref "PCIE") (pin "7") (pinfunction "PET_P3_7") (pintype "bidirectional"))
    )
    (net (code "276") (name "unconnected-(PI1-Pad63)") (class "Default")
      (node (ref "PI1") (pin "63") (pinfunction "63_63") (pintype "passive"))
    )
    (net (code "277") (name "unconnected-(PI1-Pad67)") (class "Default")
      (node (ref "PI1") (pin "67") (pinfunction "67_67") (pintype "passive"))
    )
    (net (code "278") (name "unconnected-(PI1-Pad69)") (class "Default")
      (node (ref "PI1") (pin "69") (pinfunction "69_69") (pintype "passive"))
    )
    (net (code "279") (name "unconnected-(PI1-Pad71)") (class "Default")
      (node (ref "PI1") (pin "71") (pinfunction "71_71") (pintype "passive"))
    )
    (net (code "280") (name "unconnected-(PI1-Pad74)") (class "Default")
      (node (ref "PI1") (pin "74") (pinfunction "74_74") (pintype "passive"))
    )
    (net (code "281") (name "unconnected-(SD1-DET_A-PadDET1)") (class "Default")
      (node (ref "SD1") (pin "DET1") (pinfunction "DET_A_DET1") (pintype "bidirectional"))
    )
    (net (code "282") (name "unconnected-(SD1-DET_B-PadDET2)") (class "Default")
      (node (ref "SD1") (pin "DET2") (pinfunction "DET_B_DET2") (pintype "bidirectional"))
    )
    (net (code "283") (name "unconnected-(USBC-SBU1-PadA8)") (class "Default")
      (node (ref "USBC") (pin "A8") (pinfunction "SBU1_A8") (pintype "passive"))
    )
    (net (code "284") (name "unconnected-(USBC-SBU2-PadB8)") (class "Default")
      (node (ref "USBC") (pin "B8") (pinfunction "SBU2_B8") (pintype "passive"))
    )
    (net (code "285") (name "~{ADC_RST}") (class "Default")
      (node (ref "CON2") (pin "25") (pinfunction "25_25") (pintype "bidirectional"))
      (node (ref "MODULE_AIO") (pin "A12") (pinfunction "12_A12") (pintype "passive"))
    )
  )
)
